# pcb_knx-valve-control_v1_2.net
KiCad netlist of a schematic drawn in EasyEDA
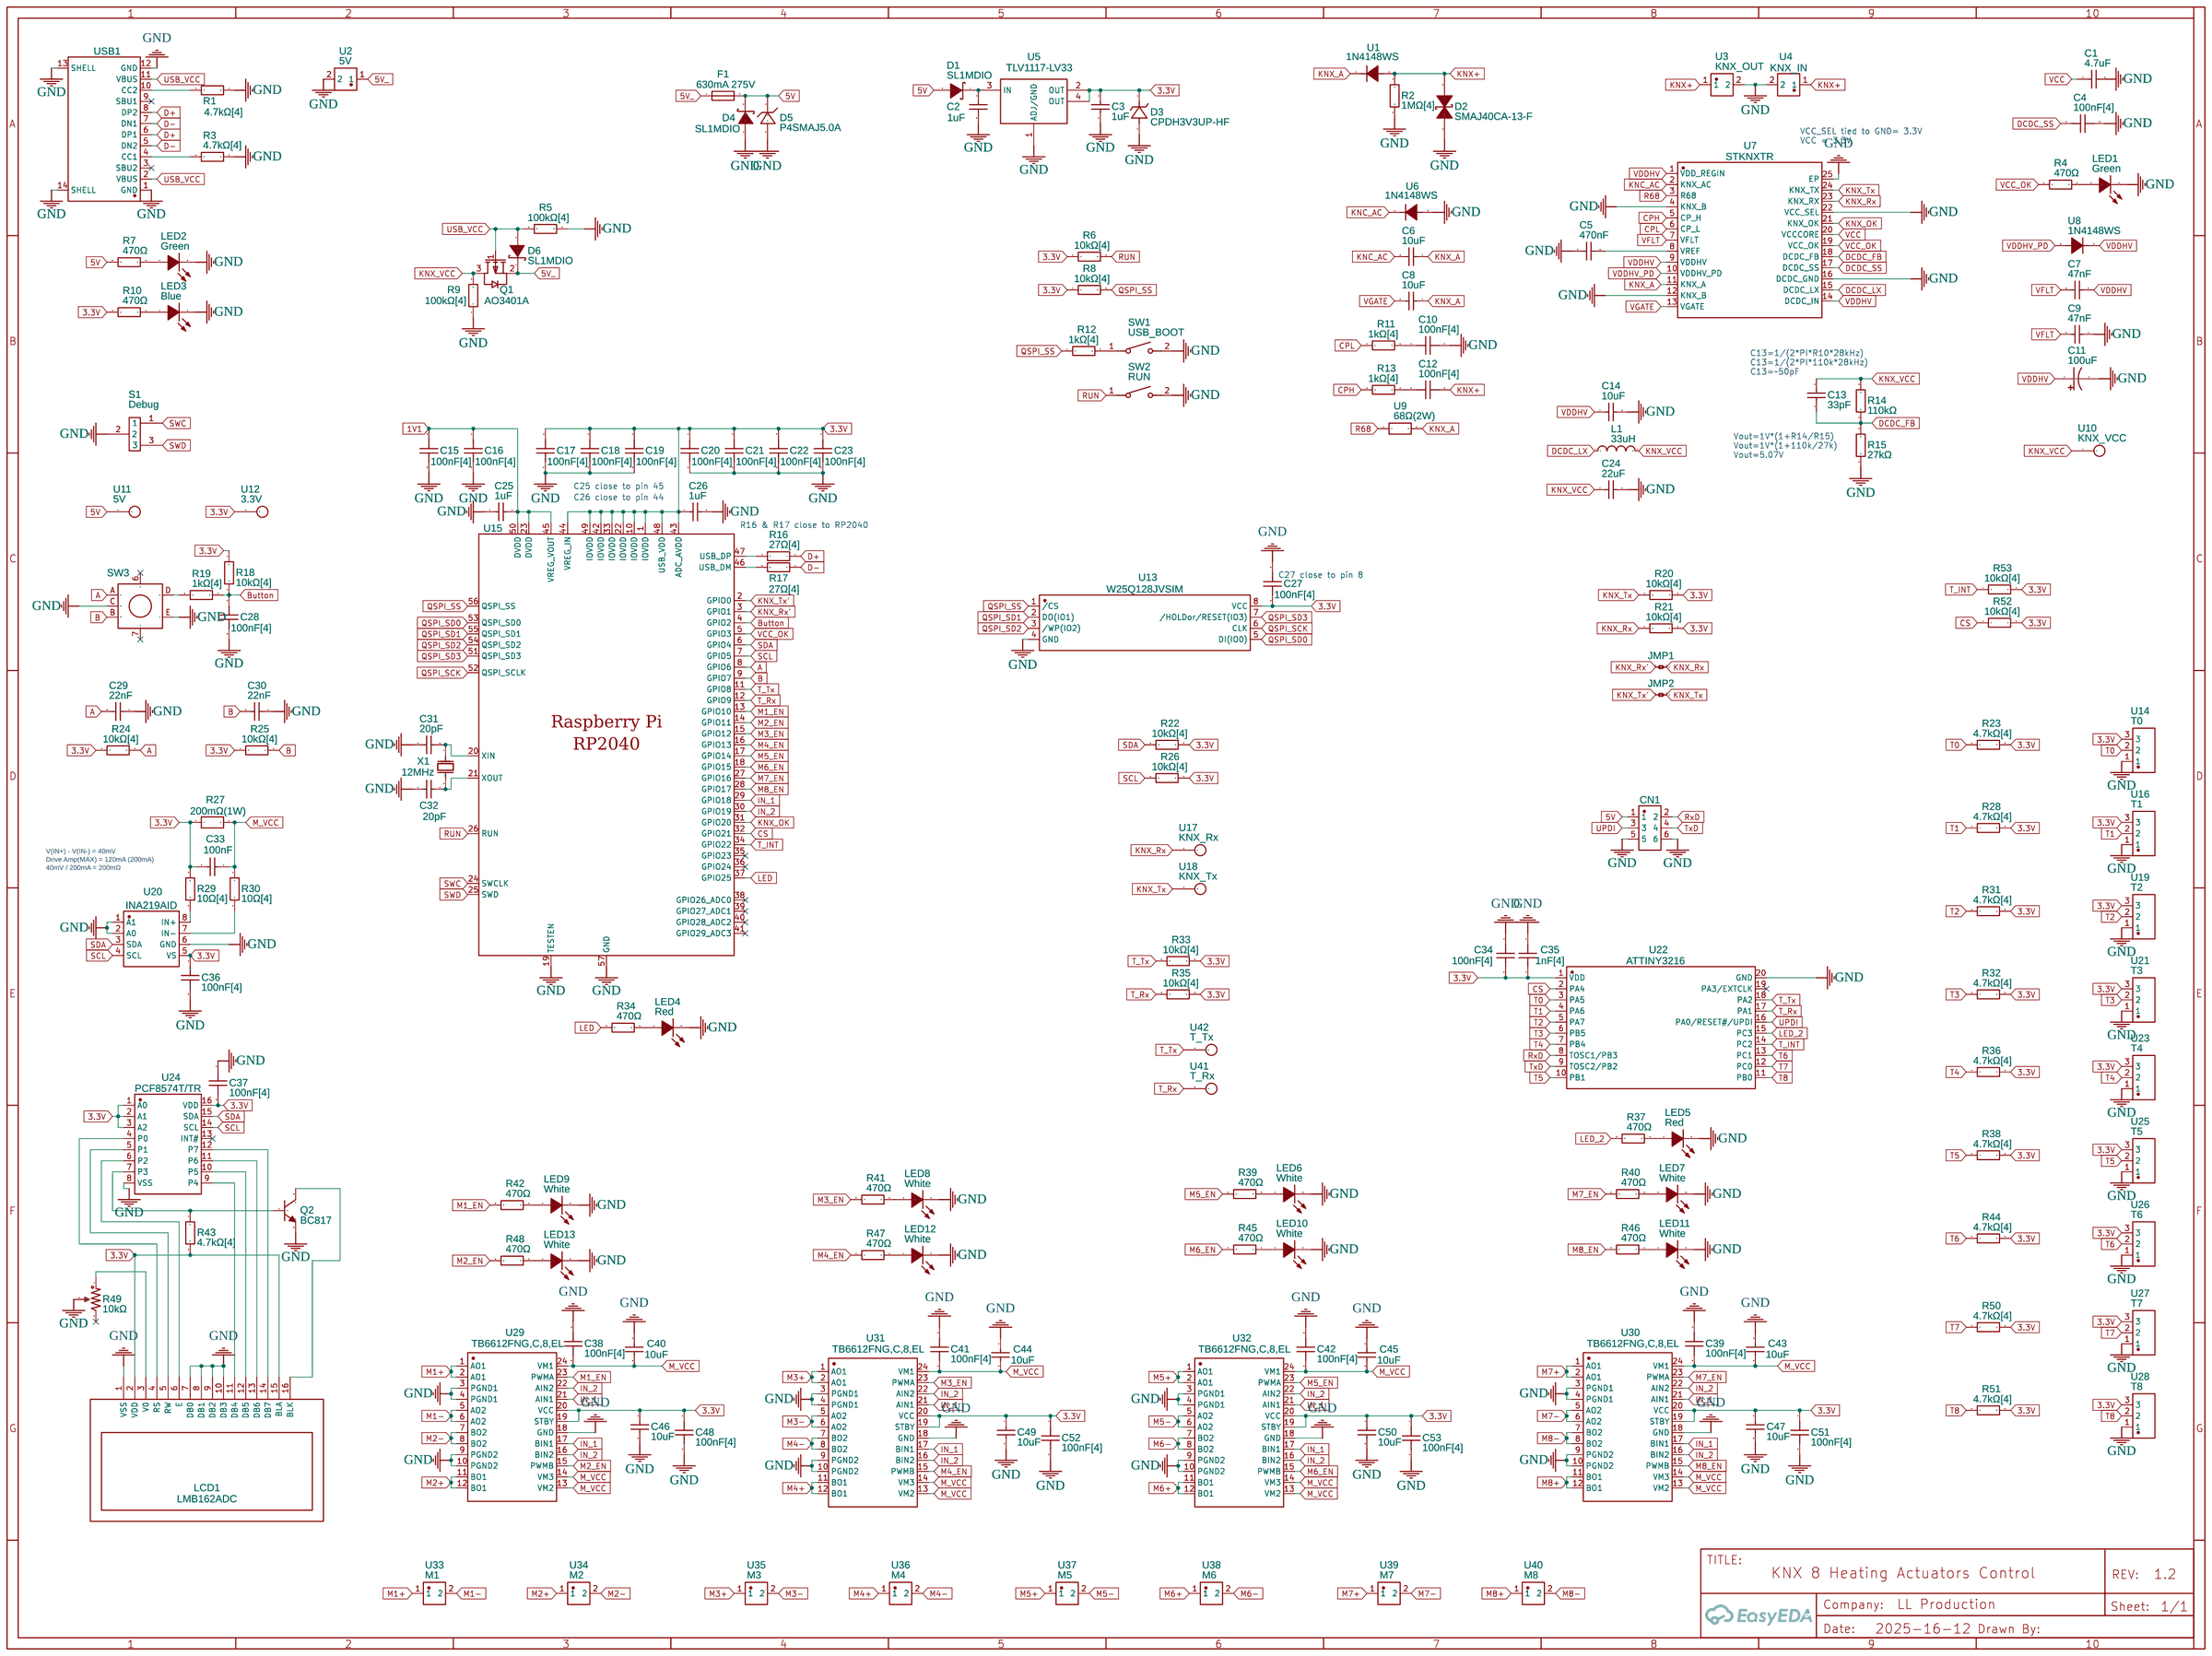
[diagram p0: schematic sheet]

(export (version "E")
  (design (tool "Eeschema 10.0.6"))
  (components
    (comp (ref "C1")
      (value "4.7uF")
      (fields (field (name "Manufacturer Part") "CC0603KRX7R9BB103") (field (name "Manufacturer") "YAGEO"))
      (libsource (lib "") (part "CC0603KRX7R9BB103_2"))
    )
    (comp (ref "C2")
      (value "1uF")
      (fields (field (name "Manufacturer Part") "CC0603KRX7R9BB103") (field (name "Manufacturer") "YAGEO"))
      (libsource (lib "") (part "CC0603KRX7R9BB103_3"))
    )
    (comp (ref "C3")
      (value "1uF")
      (fields (field (name "Manufacturer Part") "CC0603KRX7R9BB103") (field (name "Manufacturer") "YAGEO"))
      (libsource (lib "") (part "CC0603KRX7R9BB103_3"))
    )
    (comp (ref "C4")
      (value "100nF[4]")
      (fields
        (field (name "Manufacturer Part") "GRM155R71H104KE14D")
        (field (name "Manufacturer") "muRata(村田)")
      )
      (libsource (lib "") (part "GRM155R71H104KE14D_1"))
    )
    (comp (ref "C5")
      (value "470nF")
      (fields (field (name "Manufacturer Part") "CC0603KRX7R9BB103") (field (name "Manufacturer") "YAGEO"))
      (libsource (lib "") (part "CC0603KRX7R9BB103_1"))
    )
    (comp (ref "C6")
      (value "10uF")
      (fields (field (name "Manufacturer Part") "CC0603KRX7R9BB103") (field (name "Manufacturer") "YAGEO"))
      (libsource (lib "") (part "CC0603KRX7R9BB103_2"))
    )
    (comp (ref "C7")
      (value "47nF")
      (fields (field (name "Manufacturer Part") "CC0603KRX7R9BB103") (field (name "Manufacturer") "YAGEO"))
      (libsource (lib "") (part "CC0603KRX7R9BB103_2"))
    )
    (comp (ref "C8")
      (value "10uF")
      (fields (field (name "Manufacturer Part") "CC0603KRX7R9BB103") (field (name "Manufacturer") "YAGEO"))
      (libsource (lib "") (part "CC0603KRX7R9BB103_2"))
    )
    (comp (ref "C9")
      (value "47nF")
      (fields (field (name "Manufacturer Part") "CC0603KRX7R9BB103") (field (name "Manufacturer") "YAGEO"))
      (libsource (lib "") (part "CC0603KRX7R9BB103_2"))
    )
    (comp (ref "C10")
      (value "100nF[4]")
      (fields
        (field (name "Manufacturer Part") "GRM155R71H104KE14D")
        (field (name "Manufacturer") "muRata(村田)")
      )
      (libsource (lib "") (part "GRM155R71H104KE14D_1"))
    )
    (comp (ref "C11")
      (value "100uF")
      (fields (field (name "Manufacturer Part") "VEJ101M1HTR-0810") (field (name "Manufacturer") "Lelon(立隆)"))
      (libsource (lib "") (part "VEJ101M1HTR-0810"))
    )
    (comp (ref "C12")
      (value "100nF[4]")
      (fields
        (field (name "Manufacturer Part") "GRM155R71H104KE14D")
        (field (name "Manufacturer") "muRata(村田)")
      )
      (libsource (lib "") (part "GRM155R71H104KE14D_1"))
    )
    (comp (ref "C13")
      (value "33pF")
      (fields (field (name "Manufacturer Part") "CC0603KRX7R9BB103") (field (name "Manufacturer") "YAGEO"))
      (libsource (lib "") (part "CC0603KRX7R9BB103"))
    )
    (comp (ref "C14")
      (value "10uF")
      (fields (field (name "Manufacturer Part") "CC0603KRX7R9BB103") (field (name "Manufacturer") "YAGEO"))
      (libsource (lib "") (part "CC0603KRX7R9BB103_1"))
    )
    (comp (ref "C15")
      (value "100nF[4]")
      (fields
        (field (name "Manufacturer Part") "GRM155R71H104KE14D")
        (field (name "Manufacturer") "muRata(村田)")
      )
      (libsource (lib "") (part "GRM155R71H104KE14D"))
    )
    (comp (ref "C16")
      (value "100nF[4]")
      (fields
        (field (name "Manufacturer Part") "GRM155R71H104KE14D")
        (field (name "Manufacturer") "muRata(村田)")
      )
      (libsource (lib "") (part "GRM155R71H104KE14D"))
    )
    (comp (ref "C17")
      (value "100nF[4]")
      (fields
        (field (name "Manufacturer Part") "GRM155R71H104KE14D")
        (field (name "Manufacturer") "muRata(村田)")
      )
      (libsource (lib "") (part "GRM155R71H104KE14D"))
    )
    (comp (ref "C18")
      (value "100nF[4]")
      (fields
        (field (name "Manufacturer Part") "GRM155R71H104KE14D")
        (field (name "Manufacturer") "muRata(村田)")
      )
      (libsource (lib "") (part "GRM155R71H104KE14D"))
    )
    (comp (ref "C19")
      (value "100nF[4]")
      (fields
        (field (name "Manufacturer Part") "GRM155R71H104KE14D")
        (field (name "Manufacturer") "muRata(村田)")
      )
      (libsource (lib "") (part "GRM155R71H104KE14D"))
    )
    (comp (ref "C20")
      (value "100nF[4]")
      (fields
        (field (name "Manufacturer Part") "GRM155R71H104KE14D")
        (field (name "Manufacturer") "muRata(村田)")
      )
      (libsource (lib "") (part "GRM155R71H104KE14D"))
    )
    (comp (ref "C21")
      (value "100nF[4]")
      (fields
        (field (name "Manufacturer Part") "GRM155R71H104KE14D")
        (field (name "Manufacturer") "muRata(村田)")
      )
      (libsource (lib "") (part "GRM155R71H104KE14D"))
    )
    (comp (ref "C22")
      (value "100nF[4]")
      (fields
        (field (name "Manufacturer Part") "GRM155R71H104KE14D")
        (field (name "Manufacturer") "muRata(村田)")
      )
      (libsource (lib "") (part "GRM155R71H104KE14D"))
    )
    (comp (ref "C23")
      (value "100nF[4]")
      (fields
        (field (name "Manufacturer Part") "GRM155R71H104KE14D")
        (field (name "Manufacturer") "muRata(村田)")
      )
      (libsource (lib "") (part "GRM155R71H104KE14D"))
    )
    (comp (ref "C24")
      (value "22uF")
      (fields (field (name "Manufacturer Part") "CC0603KRX7R9BB103") (field (name "Manufacturer") "YAGEO"))
      (libsource (lib "") (part "CC0603KRX7R9BB103_1"))
    )
    (comp (ref "C25")
      (value "1uF")
      (fields (field (name "Manufacturer Part") "CC0603KRX7R9BB103") (field (name "Manufacturer") "YAGEO"))
      (libsource (lib "") (part "CC0603KRX7R9BB103_1"))
    )
    (comp (ref "C26")
      (value "1uF")
      (fields (field (name "Manufacturer Part") "CC0603KRX7R9BB103") (field (name "Manufacturer") "YAGEO"))
      (libsource (lib "") (part "CC0603KRX7R9BB103_1"))
    )
    (comp (ref "C27")
      (value "100nF[4]")
      (fields
        (field (name "Manufacturer Part") "GRM155R71H104KE14D")
        (field (name "Manufacturer") "muRata(村田)")
      )
      (libsource (lib "") (part "GRM155R71H104KE14D"))
    )
    (comp (ref "C28")
      (value "100nF[4]")
      (fields
        (field (name "Manufacturer Part") "GRM155R71H104KE14D")
        (field (name "Manufacturer") "muRata(村田)")
      )
      (libsource (lib "") (part "GRM155R71H104KE14D"))
    )
    (comp (ref "C29")
      (value "22nF")
      (fields (field (name "Manufacturer Part") "CC0603KRX7R9BB103") (field (name "Manufacturer") "YAGEO"))
      (libsource (lib "") (part "CC0603KRX7R9BB103_2"))
    )
    (comp (ref "C30")
      (value "22nF")
      (fields (field (name "Manufacturer Part") "CC0603KRX7R9BB103") (field (name "Manufacturer") "YAGEO"))
      (libsource (lib "") (part "CC0603KRX7R9BB103_2"))
    )
    (comp (ref "C31")
      (value "20pF")
      (fields (field (name "Manufacturer Part") "CC0603KRX7R9BB103") (field (name "Manufacturer") "YAGEO"))
      (libsource (lib "") (part "CC0603KRX7R9BB103_1"))
    )
    (comp (ref "C32")
      (value "20pF")
      (fields (field (name "Manufacturer Part") "CC0603KRX7R9BB103") (field (name "Manufacturer") "YAGEO"))
      (libsource (lib "") (part "CC0603KRX7R9BB103_1"))
    )
    (comp (ref "C33")
      (value "100nF")
      (fields (field (name "Manufacturer Part") "CC0603KRX7R9BB103") (field (name "Manufacturer") "YAGEO"))
      (libsource (lib "") (part "CC0603KRX7R9BB103_2"))
    )
    (comp (ref "C34")
      (value "100nF[4]")
      (fields
        (field (name "Manufacturer Part") "GRM155R71H104KE14D")
        (field (name "Manufacturer") "muRata(村田)")
      )
      (libsource (lib "") (part "GRM155R71H104KE14D"))
    )
    (comp (ref "C35")
      (value "1nF[4]")
      (fields
        (field (name "Manufacturer Part") "GRM155R71H104KE14D")
        (field (name "Manufacturer") "muRata(村田)")
      )
      (libsource (lib "") (part "GRM155R71H104KE14D"))
    )
    (comp (ref "C36")
      (value "100nF[4]")
      (fields
        (field (name "Manufacturer Part") "GRM155R71H104KE14D")
        (field (name "Manufacturer") "muRata(村田)")
      )
      (libsource (lib "") (part "GRM155R71H104KE14D"))
    )
    (comp (ref "C37")
      (value "100nF[4]")
      (fields
        (field (name "Manufacturer Part") "GRM155R71H104KE14D")
        (field (name "Manufacturer") "muRata(村田)")
      )
      (libsource (lib "") (part "GRM155R71H104KE14D"))
    )
    (comp (ref "C38")
      (value "100nF[4]")
      (fields
        (field (name "Manufacturer Part") "GRM155R71H104KE14D")
        (field (name "Manufacturer") "muRata(村田)")
      )
      (libsource (lib "") (part "GRM155R71H104KE14D"))
    )
    (comp (ref "C39")
      (value "100nF[4]")
      (fields
        (field (name "Manufacturer Part") "GRM155R71H104KE14D")
        (field (name "Manufacturer") "muRata(村田)")
      )
      (libsource (lib "") (part "GRM155R71H104KE14D"))
    )
    (comp (ref "C40")
      (value "10uF")
      (fields (field (name "Manufacturer Part") "CC0603KRX7R9BB103") (field (name "Manufacturer") "YAGEO"))
      (libsource (lib "") (part "CC0603KRX7R9BB103"))
    )
    (comp (ref "C41")
      (value "100nF[4]")
      (fields
        (field (name "Manufacturer Part") "GRM155R71H104KE14D")
        (field (name "Manufacturer") "muRata(村田)")
      )
      (libsource (lib "") (part "GRM155R71H104KE14D"))
    )
    (comp (ref "C42")
      (value "100nF[4]")
      (fields
        (field (name "Manufacturer Part") "GRM155R71H104KE14D")
        (field (name "Manufacturer") "muRata(村田)")
      )
      (libsource (lib "") (part "GRM155R71H104KE14D"))
    )
    (comp (ref "C43")
      (value "10uF")
      (fields (field (name "Manufacturer Part") "CC0603KRX7R9BB103") (field (name "Manufacturer") "YAGEO"))
      (libsource (lib "") (part "CC0603KRX7R9BB103"))
    )
    (comp (ref "C44")
      (value "10uF")
      (fields (field (name "Manufacturer Part") "CC0603KRX7R9BB103") (field (name "Manufacturer") "YAGEO"))
      (libsource (lib "") (part "CC0603KRX7R9BB103"))
    )
    (comp (ref "C45")
      (value "10uF")
      (fields (field (name "Manufacturer Part") "CC0603KRX7R9BB103") (field (name "Manufacturer") "YAGEO"))
      (libsource (lib "") (part "CC0603KRX7R9BB103"))
    )
    (comp (ref "C46")
      (value "10uF")
      (fields (field (name "Manufacturer Part") "CC0603KRX7R9BB103") (field (name "Manufacturer") "YAGEO"))
      (libsource (lib "") (part "CC0603KRX7R9BB103"))
    )
    (comp (ref "C47")
      (value "10uF")
      (fields (field (name "Manufacturer Part") "CC0603KRX7R9BB103") (field (name "Manufacturer") "YAGEO"))
      (libsource (lib "") (part "CC0603KRX7R9BB103"))
    )
    (comp (ref "C48")
      (value "100nF[4]")
      (fields
        (field (name "Manufacturer Part") "GRM155R71H104KE14D")
        (field (name "Manufacturer") "muRata(村田)")
      )
      (libsource (lib "") (part "GRM155R71H104KE14D"))
    )
    (comp (ref "C49")
      (value "10uF")
      (fields (field (name "Manufacturer Part") "CC0603KRX7R9BB103") (field (name "Manufacturer") "YAGEO"))
      (libsource (lib "") (part "CC0603KRX7R9BB103"))
    )
    (comp (ref "C50")
      (value "10uF")
      (fields (field (name "Manufacturer Part") "CC0603KRX7R9BB103") (field (name "Manufacturer") "YAGEO"))
      (libsource (lib "") (part "CC0603KRX7R9BB103"))
    )
    (comp (ref "C51")
      (value "100nF[4]")
      (fields
        (field (name "Manufacturer Part") "GRM155R71H104KE14D")
        (field (name "Manufacturer") "muRata(村田)")
      )
      (libsource (lib "") (part "GRM155R71H104KE14D"))
    )
    (comp (ref "C52")
      (value "100nF[4]")
      (fields
        (field (name "Manufacturer Part") "GRM155R71H104KE14D")
        (field (name "Manufacturer") "muRata(村田)")
      )
      (libsource (lib "") (part "GRM155R71H104KE14D"))
    )
    (comp (ref "C53")
      (value "100nF[4]")
      (fields
        (field (name "Manufacturer Part") "GRM155R71H104KE14D")
        (field (name "Manufacturer") "muRata(村田)")
      )
      (libsource (lib "") (part "GRM155R71H104KE14D"))
    )
    (comp (ref "CN1")
      (value "321006SG0ABK00A01")
      (fields (field (name "Manufacturer") "JILN(锦凌)"))
      (libsource (lib "") (part "321006SG0ABK00A01"))
    )
    (comp (ref "D1")
      (value "SL1MDIO")
      (fields (field (name "Manufacturer Part") "1N5819HW-7-F") (field (name "Manufacturer") "DIODES(美台)"))
      (libsource (lib "") (part "1N5819HW-7-F"))
    )
    (comp (ref "D2")
      (value "SMAJ40CA-13-F")
      (fields (field (name "Manufacturer") "DIODES(美台)"))
      (libsource (lib "") (part "SMAJ40CA-13-F"))
    )
    (comp (ref "D3")
      (value "CPDH3V3UP-HF")
      (fields (field (name "Manufacturer Part") "SOD-523"))
      (libsource (lib "") (part "SOD-523"))
    )
    (comp (ref "D4")
      (value "SL1MDIO")
      (fields (field (name "Manufacturer Part") "1N5819HW-7-F") (field (name "Manufacturer") "DIODES(美台)"))
      (libsource (lib "") (part "1N5819HW-7-F_1"))
    )
    (comp (ref "D5")
      (value "P4SMAJ5.0A")
      (fields
        (field (name "Manufacturer Part") "P4SMAJ12A_R1_00001")
        (field (name "Manufacturer") "PANJIT(强茂)")
      )
      (libsource (lib "") (part "P4SMAJ12A-PEC"))
    )
    (comp (ref "D6")
      (value "SL1MDIO")
      (fields (field (name "Manufacturer Part") "1N5819HW-7-F") (field (name "Manufacturer") "DIODES(美台)"))
      (libsource (lib "") (part "1N5819HW-7-F_2"))
    )
    (comp (ref "F1")
      (value "630mA 275V")
      (fields (field (name "Manufacturer Part") "S1032-F-60.0A") (field (name "Manufacturer") "SART(萨特)"))
      (libsource (lib "") (part "S1032-F-60.0A"))
    )
    (comp (ref "JMP1") (value "Rx") (libsource (lib "") (part "JMP-2-NO-0603")))
    (comp (ref "JMP2") (value "Rx") (libsource (lib "") (part "JMP-2-NO-0603")))
    (comp (ref "L1")
      (value "33uH")
      (fields
        (field (name "Manufacturer Part") "NR5040T330M")
        (field (name "Manufacturer") "TAIYO YUDEN(太诱)")
      )
      (libsource (lib "") (part "NR5040T330M"))
    )
    (comp (ref "LCD1")
      (value "LMB162ADC")
      (fields (field (name "Manufacturer") "TOPWAY"))
      (libsource (lib "") (part "LMB162ADC"))
    )
    (comp (ref "LED1")
      (value "Green")
      (fields (field (name "Manufacturer Part") "SZYY0603R") (field (name "Manufacturer") "yongyu(永裕光电)"))
      (libsource (lib "") (part "SZYY0603R"))
    )
    (comp (ref "LED2")
      (value "Green")
      (fields (field (name "Manufacturer Part") "SZYY0603R") (field (name "Manufacturer") "yongyu(永裕光电)"))
      (libsource (lib "") (part "SZYY0603R"))
    )
    (comp (ref "LED3")
      (value "Blue")
      (fields (field (name "Manufacturer Part") "SZYY0603R") (field (name "Manufacturer") "yongyu(永裕光电)"))
      (libsource (lib "") (part "SZYY0603R"))
    )
    (comp (ref "LED4")
      (value "Red")
      (fields (field (name "Manufacturer Part") "SZYY0603R") (field (name "Manufacturer") "yongyu(永裕光电)"))
      (libsource (lib "") (part "SZYY0603R"))
    )
    (comp (ref "LED5")
      (value "Red")
      (fields (field (name "Manufacturer Part") "SZYY0603R") (field (name "Manufacturer") "yongyu(永裕光电)"))
      (libsource (lib "") (part "SZYY0603R"))
    )
    (comp (ref "LED6")
      (value "White")
      (fields (field (name "Manufacturer Part") "SZYY0603R") (field (name "Manufacturer") "yongyu(永裕光电)"))
      (libsource (lib "") (part "SZYY0603R"))
    )
    (comp (ref "LED7")
      (value "White")
      (fields (field (name "Manufacturer Part") "SZYY0603R") (field (name "Manufacturer") "yongyu(永裕光电)"))
      (libsource (lib "") (part "SZYY0603R"))
    )
    (comp (ref "LED8")
      (value "White")
      (fields (field (name "Manufacturer Part") "SZYY0603R") (field (name "Manufacturer") "yongyu(永裕光电)"))
      (libsource (lib "") (part "SZYY0603R"))
    )
    (comp (ref "LED9")
      (value "White")
      (fields (field (name "Manufacturer Part") "SZYY0603R") (field (name "Manufacturer") "yongyu(永裕光电)"))
      (libsource (lib "") (part "SZYY0603R"))
    )
    (comp (ref "LED10")
      (value "White")
      (fields (field (name "Manufacturer Part") "SZYY0603R") (field (name "Manufacturer") "yongyu(永裕光电)"))
      (libsource (lib "") (part "SZYY0603R"))
    )
    (comp (ref "LED11")
      (value "White")
      (fields (field (name "Manufacturer Part") "SZYY0603R") (field (name "Manufacturer") "yongyu(永裕光电)"))
      (libsource (lib "") (part "SZYY0603R"))
    )
    (comp (ref "LED12")
      (value "White")
      (fields (field (name "Manufacturer Part") "SZYY0603R") (field (name "Manufacturer") "yongyu(永裕光电)"))
      (libsource (lib "") (part "SZYY0603R"))
    )
    (comp (ref "LED13")
      (value "White")
      (fields (field (name "Manufacturer Part") "SZYY0603R") (field (name "Manufacturer") "yongyu(永裕光电)"))
      (libsource (lib "") (part "SZYY0603R"))
    )
    (comp (ref "Q1")
      (value "AO3401A")
      (fields (field (name "Manufacturer") "HUASHUO(华朔)"))
      (libsource (lib "") (part "AO3401A_C700954"))
    )
    (comp (ref "Q2")
      (value "BC817")
      (fields (field (name "Manufacturer Part") "BC817-40,215") (field (name "Manufacturer") "Nexperia(安世)"))
      (libsource (lib "") (part "BC817-40,215"))
    )
    (comp (ref "R1")
      (value "4.7kΩ[4]")
      (fields
        (field (name "Manufacturer Part") "0402WGF1002TCE")
        (field (name "Manufacturer") "UNI-ROYAL(厚声)")
      )
      (libsource (lib "") (part "0402WGF1002TCE_2"))
    )
    (comp (ref "R2")
      (value "1MΩ[4]")
      (fields
        (field (name "Manufacturer Part") "0402WGF1002TCE")
        (field (name "Manufacturer") "UNI-ROYAL(厚声)")
      )
      (libsource (lib "") (part "0402WGF1002TCE_3"))
    )
    (comp (ref "R3")
      (value "4.7kΩ[4]")
      (fields
        (field (name "Manufacturer Part") "0402WGF1002TCE")
        (field (name "Manufacturer") "UNI-ROYAL(厚声)")
      )
      (libsource (lib "") (part "0402WGF1002TCE_2"))
    )
    (comp (ref "R4")
      (value "470Ω")
      (fields (field (name "Manufacturer Part") "CR0603FA1001G") (field (name "Manufacturer") "LIZ(丽智电子)"))
      (libsource (lib "") (part "CR0603FA1001G_C126900"))
    )
    (comp (ref "R5")
      (value "100kΩ[4]")
      (fields
        (field (name "Manufacturer Part") "0402WGF1002TCE")
        (field (name "Manufacturer") "UNI-ROYAL(厚声)")
      )
      (libsource (lib "") (part "0402WGF1002TCE"))
    )
    (comp (ref "R6")
      (value "10kΩ[4]")
      (fields
        (field (name "Manufacturer Part") "0402WGF1002TCE")
        (field (name "Manufacturer") "UNI-ROYAL(厚声)")
      )
      (libsource (lib "") (part "0402WGF1002TCE"))
    )
    (comp (ref "R7")
      (value "470Ω")
      (fields (field (name "Manufacturer Part") "CR0603FA1001G") (field (name "Manufacturer") "LIZ(丽智电子)"))
      (libsource (lib "") (part "CR0603FA1001G_C126900"))
    )
    (comp (ref "R8")
      (value "10kΩ[4]")
      (fields
        (field (name "Manufacturer Part") "0402WGF1002TCE")
        (field (name "Manufacturer") "UNI-ROYAL(厚声)")
      )
      (libsource (lib "") (part "0402WGF1002TCE"))
    )
    (comp (ref "R9")
      (value "100kΩ[4]")
      (fields
        (field (name "Manufacturer Part") "0402WGF1002TCE")
        (field (name "Manufacturer") "UNI-ROYAL(厚声)")
      )
      (libsource (lib "") (part "0402WGF1002TCE_1"))
    )
    (comp (ref "R10")
      (value "470Ω")
      (fields (field (name "Manufacturer Part") "CR0603FA1001G") (field (name "Manufacturer") "LIZ(丽智电子)"))
      (libsource (lib "") (part "CR0603FA1001G_C126900"))
    )
    (comp (ref "R11")
      (value "1kΩ[4]")
      (fields
        (field (name "Manufacturer Part") "0402WGF1002TCE")
        (field (name "Manufacturer") "UNI-ROYAL(厚声)")
      )
      (libsource (lib "") (part "0402WGF1002TCE"))
    )
    (comp (ref "R12")
      (value "1kΩ[4]")
      (fields
        (field (name "Manufacturer Part") "0402WGF1002TCE")
        (field (name "Manufacturer") "UNI-ROYAL(厚声)")
      )
      (libsource (lib "") (part "0402WGF1002TCE"))
    )
    (comp (ref "R13")
      (value "1kΩ[4]")
      (fields
        (field (name "Manufacturer Part") "0402WGF1002TCE")
        (field (name "Manufacturer") "UNI-ROYAL(厚声)")
      )
      (libsource (lib "") (part "0402WGF1002TCE"))
    )
    (comp (ref "R14")
      (value "110kΩ")
      (fields (field (name "Manufacturer Part") "CR0603FA1001G") (field (name "Manufacturer") "LIZ(丽智电子)"))
      (libsource (lib "") (part "CR0603FA1001G_C126900_1"))
    )
    (comp (ref "R15")
      (value "27kΩ")
      (fields (field (name "Manufacturer Part") "CR0603FA1001G") (field (name "Manufacturer") "LIZ(丽智电子)"))
      (libsource (lib "") (part "CR0603FA1001G_C126900_1"))
    )
    (comp (ref "R16")
      (value "27Ω[4]")
      (fields
        (field (name "Manufacturer Part") "0402WGF1002TCE")
        (field (name "Manufacturer") "UNI-ROYAL(厚声)")
      )
      (libsource (lib "") (part "0402WGF1002TCE_2"))
    )
    (comp (ref "R17")
      (value "27Ω[4]")
      (fields
        (field (name "Manufacturer Part") "0402WGF1002TCE")
        (field (name "Manufacturer") "UNI-ROYAL(厚声)")
      )
      (libsource (lib "") (part "0402WGF1002TCE_2"))
    )
    (comp (ref "R18")
      (value "10kΩ[4]")
      (fields
        (field (name "Manufacturer Part") "0402WGF1002TCE")
        (field (name "Manufacturer") "UNI-ROYAL(厚声)")
      )
      (libsource (lib "") (part "0402WGF1002TCE_3"))
    )
    (comp (ref "R19")
      (value "1kΩ[4]")
      (fields
        (field (name "Manufacturer Part") "0402WGF1002TCE")
        (field (name "Manufacturer") "UNI-ROYAL(厚声)")
      )
      (libsource (lib "") (part "0402WGF1002TCE_2"))
    )
    (comp (ref "R20")
      (value "10kΩ[4]")
      (fields
        (field (name "Manufacturer Part") "0402WGF1002TCE")
        (field (name "Manufacturer") "UNI-ROYAL(厚声)")
      )
      (libsource (lib "") (part "0402WGF1002TCE"))
    )
    (comp (ref "R21")
      (value "10kΩ[4]")
      (fields
        (field (name "Manufacturer Part") "0402WGF1002TCE")
        (field (name "Manufacturer") "UNI-ROYAL(厚声)")
      )
      (libsource (lib "") (part "0402WGF1002TCE"))
    )
    (comp (ref "R22")
      (value "10kΩ[4]")
      (fields
        (field (name "Manufacturer Part") "0402WGF1002TCE")
        (field (name "Manufacturer") "UNI-ROYAL(厚声)")
      )
      (libsource (lib "") (part "0402WGF1002TCE"))
    )
    (comp (ref "R23")
      (value "4.7kΩ[4]")
      (fields
        (field (name "Manufacturer Part") "0402WGF1002TCE")
        (field (name "Manufacturer") "UNI-ROYAL(厚声)")
      )
      (libsource (lib "") (part "0402WGF1002TCE"))
    )
    (comp (ref "R24")
      (value "10kΩ[4]")
      (fields
        (field (name "Manufacturer Part") "0402WGF1002TCE")
        (field (name "Manufacturer") "UNI-ROYAL(厚声)")
      )
      (libsource (lib "") (part "0402WGF1002TCE"))
    )
    (comp (ref "R25")
      (value "10kΩ[4]")
      (fields
        (field (name "Manufacturer Part") "0402WGF1002TCE")
        (field (name "Manufacturer") "UNI-ROYAL(厚声)")
      )
      (libsource (lib "") (part "0402WGF1002TCE"))
    )
    (comp (ref "R26")
      (value "10kΩ[4]")
      (fields
        (field (name "Manufacturer Part") "0402WGF1002TCE")
        (field (name "Manufacturer") "UNI-ROYAL(厚声)")
      )
      (libsource (lib "") (part "0402WGF1002TCE"))
    )
    (comp (ref "R27")
      (value "200mΩ(1W)")
      (fields (field (name "Manufacturer Part") "SCR1206F1M1") (field (name "Manufacturer") "VO(翔胜)"))
      (libsource (lib "") (part "SCR1206F1M1"))
    )
    (comp (ref "R28")
      (value "4.7kΩ[4]")
      (fields
        (field (name "Manufacturer Part") "0402WGF1002TCE")
        (field (name "Manufacturer") "UNI-ROYAL(厚声)")
      )
      (libsource (lib "") (part "0402WGF1002TCE"))
    )
    (comp (ref "R29")
      (value "10Ω[4]")
      (fields
        (field (name "Manufacturer Part") "0402WGF1002TCE")
        (field (name "Manufacturer") "UNI-ROYAL(厚声)")
      )
      (libsource (lib "") (part "0402WGF1002TCE_3"))
    )
    (comp (ref "R30")
      (value "10Ω[4]")
      (fields
        (field (name "Manufacturer Part") "0402WGF1002TCE")
        (field (name "Manufacturer") "UNI-ROYAL(厚声)")
      )
      (libsource (lib "") (part "0402WGF1002TCE_3"))
    )
    (comp (ref "R31")
      (value "4.7kΩ[4]")
      (fields
        (field (name "Manufacturer Part") "0402WGF1002TCE")
        (field (name "Manufacturer") "UNI-ROYAL(厚声)")
      )
      (libsource (lib "") (part "0402WGF1002TCE"))
    )
    (comp (ref "R32")
      (value "4.7kΩ[4]")
      (fields
        (field (name "Manufacturer Part") "0402WGF1002TCE")
        (field (name "Manufacturer") "UNI-ROYAL(厚声)")
      )
      (libsource (lib "") (part "0402WGF1002TCE"))
    )
    (comp (ref "R33")
      (value "10kΩ[4]")
      (fields
        (field (name "Manufacturer Part") "0402WGF1002TCE")
        (field (name "Manufacturer") "UNI-ROYAL(厚声)")
      )
      (libsource (lib "") (part "0402WGF1002TCE"))
    )
    (comp (ref "R34")
      (value "470Ω")
      (fields (field (name "Manufacturer Part") "CR0603FA1001G") (field (name "Manufacturer") "LIZ(丽智电子)"))
      (libsource (lib "") (part "CR0603FA1001G_C126900"))
    )
    (comp (ref "R35")
      (value "10kΩ[4]")
      (fields
        (field (name "Manufacturer Part") "0402WGF1002TCE")
        (field (name "Manufacturer") "UNI-ROYAL(厚声)")
      )
      (libsource (lib "") (part "0402WGF1002TCE"))
    )
    (comp (ref "R36")
      (value "4.7kΩ[4]")
      (fields
        (field (name "Manufacturer Part") "0402WGF1002TCE")
        (field (name "Manufacturer") "UNI-ROYAL(厚声)")
      )
      (libsource (lib "") (part "0402WGF1002TCE"))
    )
    (comp (ref "R37")
      (value "470Ω")
      (fields (field (name "Manufacturer Part") "CR0603FA1001G") (field (name "Manufacturer") "LIZ(丽智电子)"))
      (libsource (lib "") (part "CR0603FA1001G_C126900"))
    )
    (comp (ref "R38")
      (value "4.7kΩ[4]")
      (fields
        (field (name "Manufacturer Part") "0402WGF1002TCE")
        (field (name "Manufacturer") "UNI-ROYAL(厚声)")
      )
      (libsource (lib "") (part "0402WGF1002TCE"))
    )
    (comp (ref "R39")
      (value "470Ω")
      (fields (field (name "Manufacturer Part") "CR0603FA1001G") (field (name "Manufacturer") "LIZ(丽智电子)"))
      (libsource (lib "") (part "CR0603FA1001G_C126900"))
    )
    (comp (ref "R40")
      (value "470Ω")
      (fields (field (name "Manufacturer Part") "CR0603FA1001G") (field (name "Manufacturer") "LIZ(丽智电子)"))
      (libsource (lib "") (part "CR0603FA1001G_C126900"))
    )
    (comp (ref "R41")
      (value "470Ω")
      (fields (field (name "Manufacturer Part") "CR0603FA1001G") (field (name "Manufacturer") "LIZ(丽智电子)"))
      (libsource (lib "") (part "CR0603FA1001G_C126900"))
    )
    (comp (ref "R42")
      (value "470Ω")
      (fields (field (name "Manufacturer Part") "CR0603FA1001G") (field (name "Manufacturer") "LIZ(丽智电子)"))
      (libsource (lib "") (part "CR0603FA1001G_C126900"))
    )
    (comp (ref "R43")
      (value "4.7kΩ[4]")
      (fields
        (field (name "Manufacturer Part") "0402WGF1002TCE")
        (field (name "Manufacturer") "UNI-ROYAL(厚声)")
      )
      (libsource (lib "") (part "0402WGF1002TCE_3"))
    )
    (comp (ref "R44")
      (value "4.7kΩ[4]")
      (fields
        (field (name "Manufacturer Part") "0402WGF1002TCE")
        (field (name "Manufacturer") "UNI-ROYAL(厚声)")
      )
      (libsource (lib "") (part "0402WGF1002TCE"))
    )
    (comp (ref "R45")
      (value "470Ω")
      (fields (field (name "Manufacturer Part") "CR0603FA1001G") (field (name "Manufacturer") "LIZ(丽智电子)"))
      (libsource (lib "") (part "CR0603FA1001G_C126900"))
    )
    (comp (ref "R46")
      (value "470Ω")
      (fields (field (name "Manufacturer Part") "CR0603FA1001G") (field (name "Manufacturer") "LIZ(丽智电子)"))
      (libsource (lib "") (part "CR0603FA1001G_C126900"))
    )
    (comp (ref "R47")
      (value "470Ω")
      (fields (field (name "Manufacturer Part") "CR0603FA1001G") (field (name "Manufacturer") "LIZ(丽智电子)"))
      (libsource (lib "") (part "CR0603FA1001G_C126900"))
    )
    (comp (ref "R48")
      (value "470Ω")
      (fields (field (name "Manufacturer Part") "CR0603FA1001G") (field (name "Manufacturer") "LIZ(丽智电子)"))
      (libsource (lib "") (part "CR0603FA1001G_C126900"))
    )
    (comp (ref "R49")
      (value "10kΩ")
      (fields (field (name "Manufacturer Part") "TC33X-2-103E") (field (name "Manufacturer") "BOURNS"))
      (libsource (lib "") (part "TC33X-2-103E"))
    )
    (comp (ref "R50")
      (value "4.7kΩ[4]")
      (fields
        (field (name "Manufacturer Part") "0402WGF1002TCE")
        (field (name "Manufacturer") "UNI-ROYAL(厚声)")
      )
      (libsource (lib "") (part "0402WGF1002TCE"))
    )
    (comp (ref "R51")
      (value "4.7kΩ[4]")
      (fields
        (field (name "Manufacturer Part") "0402WGF1002TCE")
        (field (name "Manufacturer") "UNI-ROYAL(厚声)")
      )
      (libsource (lib "") (part "0402WGF1002TCE"))
    )
    (comp (ref "R52")
      (value "10kΩ[4]")
      (fields
        (field (name "Manufacturer Part") "0402WGF1002TCE")
        (field (name "Manufacturer") "UNI-ROYAL(厚声)")
      )
      (libsource (lib "") (part "0402WGF1002TCE"))
    )
    (comp (ref "R53")
      (value "10kΩ[4]")
      (fields
        (field (name "Manufacturer Part") "0402WGF1002TCE")
        (field (name "Manufacturer") "UNI-ROYAL(厚声)")
      )
      (libsource (lib "") (part "0402WGF1002TCE"))
    )
    (comp (ref "S1") (value "Debug") (libsource (lib "") (part "3PAD_SEL")))
    (comp (ref "SW1")
      (value "USB_BOOT")
      (fields
        (field (name "Manufacturer Part") "TS-1185EC-C-D-B")
        (field (name "Manufacturer") "XKB Connection(中国星坤)")
      )
      (libsource (lib "") (part "TS-1185EC-C-D-B"))
    )
    (comp (ref "SW2")
      (value "RUN")
      (fields
        (field (name "Manufacturer Part") "TS-1185EC-C-D-B")
        (field (name "Manufacturer") "XKB Connection(中国星坤)")
      )
      (libsource (lib "") (part "TS-1185EC-C-D-B"))
    )
    (comp (ref "SW3")
      (value "EC11L1525G01")
      (fields (field (name "Manufacturer") "ALPSALPINE(阿尔卑斯阿尔派)"))
      (libsource (lib "") (part "EC11L1525G01"))
    )
    (comp (ref "U1")
      (value "1N4148WS")
      (fields (field (name "Manufacturer") "Zhengxin(正芯)"))
      (libsource (lib "") (part "1N4148WS"))
    )
    (comp (ref "U2")
      (value "5V")
      (fields (field (name "Manufacturer Part") "2P,间距5.08mm,弹片压线升降式"))
      (libsource (lib "") (part "2P,间距5.08MM,弹片压线升降式_1"))
    )
    (comp (ref "U3")
      (value "KNX_OUT")
      (fields (field (name "Manufacturer Part") "2P,间距5.08mm,弹片压线升降式"))
      (libsource (lib "") (part "2P,间距5.08MM,弹片压线升降式"))
    )
    (comp (ref "U4")
      (value "KNX_IN")
      (fields (field (name "Manufacturer Part") "2P,间距5.08mm,弹片压线升降式"))
      (libsource (lib "") (part "2P,间距5.08MM,弹片压线升降式_1"))
    )
    (comp (ref "U5")
      (value "TLV1117-LV33")
      (fields (field (name "Manufacturer Part") "TLV1117LV33DCYR") (field (name "Manufacturer") "TI(德州仪器)"))
      (libsource (lib "") (part "TLV1117LV33DCYR"))
    )
    (comp (ref "U6")
      (value "1N4148WS")
      (fields (field (name "Manufacturer") "Zhengxin(正芯)"))
      (libsource (lib "") (part "1N4148WS"))
    )
    (comp (ref "U7")
      (value "STKNXTR")
      (fields (field (name "Manufacturer") "ST(意法半导体)"))
      (libsource (lib "") (part "STKNXTR"))
    )
    (comp (ref "U8")
      (value "1N4148WS")
      (fields (field (name "Manufacturer") "Zhengxin(正芯)"))
      (libsource (lib "") (part "1N4148WS_1"))
    )
    (comp (ref "U9")
      (value "68Ω(2W)")
      (fields
        (field (name "Manufacturer Part") "HoJLR2512-3W-3.5mR-1%")
        (field (name "Manufacturer") "Milliohm(毫欧)")
      )
      (libsource (lib "") (part "HOJLR2512-3W-3.5MR-1%"))
    )
    (comp (ref "U10") (value "KNX_VCC") (libsource (lib "") (part "Through hole")))
    (comp (ref "U11") (value "5V") (libsource (lib "") (part "Through hole")))
    (comp (ref "U12") (value "3.3V") (libsource (lib "") (part "Through hole")))
    (comp (ref "U13")
      (value "W25Q128JVSIM")
      (fields (field (name "Manufacturer") "WINBOND(华邦)"))
      (libsource (lib "") (part "W25Q128JVSIM"))
    )
    (comp (ref "U14")
      (value "T0")
      (fields
        (field (name "Manufacturer Part") "DB127V-5.08-3P-GN-S")
        (field (name "Manufacturer") "DIBO(地博电气)")
      )
      (libsource (lib "") (part "DB127V-5.08-3P-GN-S"))
    )
    (comp (ref "U15")
      (value "RP2040")
      (fields (field (name "Manufacturer") "Raspberry Pi(树莓派)"))
      (libsource (lib "") (part "RP2040"))
    )
    (comp (ref "U16")
      (value "T1")
      (fields
        (field (name "Manufacturer Part") "DB127V-5.08-3P-GN-S")
        (field (name "Manufacturer") "DIBO(地博电气)")
      )
      (libsource (lib "") (part "DB127V-5.08-3P-GN-S"))
    )
    (comp (ref "U17") (value "KNX_Rx") (libsource (lib "") (part "Through hole")))
    (comp (ref "U18") (value "KNX_Tx") (libsource (lib "") (part "Through hole")))
    (comp (ref "U19")
      (value "T2")
      (fields
        (field (name "Manufacturer Part") "DB127V-5.08-3P-GN-S")
        (field (name "Manufacturer") "DIBO(地博电气)")
      )
      (libsource (lib "") (part "DB127V-5.08-3P-GN-S"))
    )
    (comp (ref "U20")
      (value "INA219AID")
      (fields (field (name "Manufacturer") "TI(德州仪器)"))
      (libsource (lib "") (part "INA219AID"))
    )
    (comp (ref "U21")
      (value "T3")
      (fields
        (field (name "Manufacturer Part") "DB127V-5.08-3P-GN-S")
        (field (name "Manufacturer") "DIBO(地博电气)")
      )
      (libsource (lib "") (part "DB127V-5.08-3P-GN-S"))
    )
    (comp (ref "U22")
      (value "ATTINY3216")
      (fields
        (field (name "Manufacturer Part") "ATTINY1616-SN")
        (field (name "Manufacturer") "MICROCHIP(美国微芯)")
      )
      (libsource (lib "") (part "ATTINY1616-SN_C614136"))
    )
    (comp (ref "U23")
      (value "T4")
      (fields
        (field (name "Manufacturer Part") "DB127V-5.08-3P-GN-S")
        (field (name "Manufacturer") "DIBO(地博电气)")
      )
      (libsource (lib "") (part "DB127V-5.08-3P-GN-S"))
    )
    (comp (ref "U24")
      (value "PCF8574T/TR")
      (fields (field (name "Manufacturer") "HGSEMI(华冠)"))
      (libsource (lib "") (part "PCF8574T/TR"))
    )
    (comp (ref "U25")
      (value "T5")
      (fields
        (field (name "Manufacturer Part") "DB127V-5.08-3P-GN-S")
        (field (name "Manufacturer") "DIBO(地博电气)")
      )
      (libsource (lib "") (part "DB127V-5.08-3P-GN-S"))
    )
    (comp (ref "U26")
      (value "T6")
      (fields
        (field (name "Manufacturer Part") "DB127V-5.08-3P-GN-S")
        (field (name "Manufacturer") "DIBO(地博电气)")
      )
      (libsource (lib "") (part "DB127V-5.08-3P-GN-S"))
    )
    (comp (ref "U27")
      (value "T7")
      (fields
        (field (name "Manufacturer Part") "DB127V-5.08-3P-GN-S")
        (field (name "Manufacturer") "DIBO(地博电气)")
      )
      (libsource (lib "") (part "DB127V-5.08-3P-GN-S"))
    )
    (comp (ref "U28")
      (value "T8")
      (fields
        (field (name "Manufacturer Part") "DB127V-5.08-3P-GN-S")
        (field (name "Manufacturer") "DIBO(地博电气)")
      )
      (libsource (lib "") (part "DB127V-5.08-3P-GN-S"))
    )
    (comp (ref "U29")
      (value "TB6612FNG,C,8,EL")
      (fields (field (name "Manufacturer") "TOSHIBA(东芝)"))
      (libsource (lib "") (part "TB6612FNG,C,8,EL"))
    )
    (comp (ref "U30")
      (value "TB6612FNG,C,8,EL")
      (fields (field (name "Manufacturer") "TOSHIBA(东芝)"))
      (libsource (lib "") (part "TB6612FNG,C,8,EL"))
    )
    (comp (ref "U31")
      (value "TB6612FNG,C,8,EL")
      (fields (field (name "Manufacturer") "TOSHIBA(东芝)"))
      (libsource (lib "") (part "TB6612FNG,C,8,EL"))
    )
    (comp (ref "U32")
      (value "TB6612FNG,C,8,EL")
      (fields (field (name "Manufacturer") "TOSHIBA(东芝)"))
      (libsource (lib "") (part "TB6612FNG,C,8,EL"))
    )
    (comp (ref "U33")
      (value "M1")
      (fields (field (name "Manufacturer Part") "2P,间距5.08mm,弹片压线升降式"))
      (libsource (lib "") (part "2P,间距5.08MM,弹片压线升降式"))
    )
    (comp (ref "U34")
      (value "M2")
      (fields (field (name "Manufacturer Part") "2P,间距5.08mm,弹片压线升降式"))
      (libsource (lib "") (part "2P,间距5.08MM,弹片压线升降式"))
    )
    (comp (ref "U35")
      (value "M3")
      (fields (field (name "Manufacturer Part") "2P,间距5.08mm,弹片压线升降式"))
      (libsource (lib "") (part "2P,间距5.08MM,弹片压线升降式"))
    )
    (comp (ref "U36")
      (value "M4")
      (fields (field (name "Manufacturer Part") "2P,间距5.08mm,弹片压线升降式"))
      (libsource (lib "") (part "2P,间距5.08MM,弹片压线升降式"))
    )
    (comp (ref "U37")
      (value "M5")
      (fields (field (name "Manufacturer Part") "2P,间距5.08mm,弹片压线升降式"))
      (libsource (lib "") (part "2P,间距5.08MM,弹片压线升降式"))
    )
    (comp (ref "U38")
      (value "M6")
      (fields (field (name "Manufacturer Part") "2P,间距5.08mm,弹片压线升降式"))
      (libsource (lib "") (part "2P,间距5.08MM,弹片压线升降式"))
    )
    (comp (ref "U39")
      (value "M7")
      (fields (field (name "Manufacturer Part") "2P,间距5.08mm,弹片压线升降式"))
      (libsource (lib "") (part "2P,间距5.08MM,弹片压线升降式"))
    )
    (comp (ref "U40")
      (value "M8")
      (fields (field (name "Manufacturer Part") "2P,间距5.08mm,弹片压线升降式"))
      (libsource (lib "") (part "2P,间距5.08MM,弹片压线升降式"))
    )
    (comp (ref "U41") (value "T_Rx") (libsource (lib "") (part "Through hole")))
    (comp (ref "U42") (value "T_Tx") (libsource (lib "") (part "Through hole")))
    (comp (ref "USB1")
      (value "TYPE-C 16PIN 2MD(073)")
      (fields (field (name "Manufacturer") "SHOU HAN(首韩)"))
      (libsource (lib "") (part "TYPE-C 16PIN 2MD(073)"))
    )
    (comp (ref "X1")
      (value "12MHz")
      (fields (field (name "Manufacturer Part") "TAXM12M2QLFCDT1T") (field (name "Manufacturer") "YJX(雅晶鑫)"))
      (libsource (lib "") (part "SMD-5032_2P 12M 20pf 30ppm"))
    )
  )
  (nets
    (net (code "1") (name "1V1") (class "Default")
      (node (ref "C15") (pin "1") (pinfunction "1_1") (pintype "unspecified"))
      (node (ref "C16") (pin "1") (pinfunction "1_1") (pintype "unspecified"))
      (node (ref "C25") (pin "2") (pinfunction "2_2") (pintype "input"))
      (node (ref "U15") (pin "23") (pinfunction "DVDD_23") (pintype "bidirectional"))
      (node (ref "U15") (pin "45") (pinfunction "VREG_VOUT_45") (pintype "bidirectional"))
      (node (ref "U15") (pin "50") (pinfunction "DVDD_50") (pintype "bidirectional"))
    )
    (net (code "2") (name "3.3V") (class "Default")
      (node (ref "C17") (pin "1") (pinfunction "1_1") (pintype "unspecified"))
      (node (ref "C18") (pin "1") (pinfunction "1_1") (pintype "unspecified"))
      (node (ref "C19") (pin "1") (pinfunction "1_1") (pintype "unspecified"))
      (node (ref "C20") (pin "1") (pinfunction "1_1") (pintype "unspecified"))
      (node (ref "C21") (pin "1") (pinfunction "1_1") (pintype "unspecified"))
      (node (ref "C22") (pin "1") (pinfunction "1_1") (pintype "unspecified"))
      (node (ref "C23") (pin "1") (pinfunction "1_1") (pintype "unspecified"))
      (node (ref "C26") (pin "1") (pinfunction "1_1") (pintype "input"))
      (node (ref "C27") (pin "2") (pinfunction "2_2") (pintype "unspecified"))
      (node (ref "C3") (pin "2") (pinfunction "2_2") (pintype "input"))
      (node (ref "C33") (pin "2") (pinfunction "2_2") (pintype "input"))
      (node (ref "C34") (pin "2") (pinfunction "2_2") (pintype "unspecified"))
      (node (ref "C35") (pin "2") (pinfunction "2_2") (pintype "unspecified"))
      (node (ref "C36") (pin "1") (pinfunction "1_1") (pintype "unspecified"))
      (node (ref "C37") (pin "2") (pinfunction "2_2") (pintype "unspecified"))
      (node (ref "C46") (pin "1") (pinfunction "1_1") (pintype "input"))
      (node (ref "C47") (pin "1") (pinfunction "1_1") (pintype "input"))
      (node (ref "C48") (pin "1") (pinfunction "1_1") (pintype "unspecified"))
      (node (ref "C49") (pin "1") (pinfunction "1_1") (pintype "input"))
      (node (ref "C50") (pin "1") (pinfunction "1_1") (pintype "input"))
      (node (ref "C51") (pin "1") (pinfunction "1_1") (pintype "unspecified"))
      (node (ref "C52") (pin "1") (pinfunction "1_1") (pintype "unspecified"))
      (node (ref "C53") (pin "1") (pinfunction "1_1") (pintype "unspecified"))
      (node (ref "D3") (pin "1") (pinfunction "K_1") (pintype "unspecified"))
      (node (ref "LCD1") (pin "15") (pinfunction "BLA_15") (pintype "unspecified"))
      (node (ref "LCD1") (pin "2") (pinfunction "VDD_2") (pintype "unspecified"))
      (node (ref "R10") (pin "2") (pinfunction "2_2") (pintype "input"))
      (node (ref "R18") (pin "1") (pinfunction "1_1") (pintype "input"))
      (node (ref "R20") (pin "2") (pinfunction "2_2") (pintype "input"))
      (node (ref "R21") (pin "2") (pinfunction "2_2") (pintype "input"))
      (node (ref "R22") (pin "2") (pinfunction "2_2") (pintype "input"))
      (node (ref "R23") (pin "2") (pinfunction "2_2") (pintype "input"))
      (node (ref "R24") (pin "1") (pinfunction "1_1") (pintype "input"))
      (node (ref "R25") (pin "1") (pinfunction "1_1") (pintype "input"))
      (node (ref "R26") (pin "2") (pinfunction "2_2") (pintype "input"))
      (node (ref "R27") (pin "1") (pinfunction "1_1") (pintype "unspecified"))
      (node (ref "R28") (pin "2") (pinfunction "2_2") (pintype "input"))
      (node (ref "R29") (pin "1") (pinfunction "1_1") (pintype "input"))
      (node (ref "R31") (pin "2") (pinfunction "2_2") (pintype "input"))
      (node (ref "R32") (pin "2") (pinfunction "2_2") (pintype "input"))
      (node (ref "R33") (pin "2") (pinfunction "2_2") (pintype "input"))
      (node (ref "R35") (pin "2") (pinfunction "2_2") (pintype "input"))
      (node (ref "R36") (pin "2") (pinfunction "2_2") (pintype "input"))
      (node (ref "R38") (pin "2") (pinfunction "2_2") (pintype "input"))
      (node (ref "R43") (pin "2") (pinfunction "2_2") (pintype "input"))
      (node (ref "R44") (pin "2") (pinfunction "2_2") (pintype "input"))
      (node (ref "R50") (pin "2") (pinfunction "2_2") (pintype "input"))
      (node (ref "R51") (pin "2") (pinfunction "2_2") (pintype "input"))
      (node (ref "R52") (pin "2") (pinfunction "2_2") (pintype "input"))
      (node (ref "R53") (pin "2") (pinfunction "2_2") (pintype "input"))
      (node (ref "R6") (pin "1") (pinfunction "1_1") (pintype "input"))
      (node (ref "R8") (pin "1") (pinfunction "1_1") (pintype "input"))
      (node (ref "U12") (pin "1") (pinfunction "1_1") (pintype "unspecified"))
      (node (ref "U13") (pin "8") (pinfunction "VCC_8") (pintype "unspecified"))
      (node (ref "U14") (pin "3") (pinfunction "3_3") (pintype "unspecified"))
      (node (ref "U15") (pin "1") (pinfunction "IOVDD_1") (pintype "bidirectional"))
      (node (ref "U15") (pin "10") (pinfunction "IOVDD_10") (pintype "bidirectional"))
      (node (ref "U15") (pin "22") (pinfunction "IOVDD_22") (pintype "bidirectional"))
      (node (ref "U15") (pin "33") (pinfunction "IOVDD_33") (pintype "bidirectional"))
      (node (ref "U15") (pin "42") (pinfunction "IOVDD_42") (pintype "bidirectional"))
      (node (ref "U15") (pin "43") (pinfunction "ADC_AVDD_43") (pintype "bidirectional"))
      (node (ref "U15") (pin "44") (pinfunction "VREG_IN_44") (pintype "bidirectional"))
      (node (ref "U15") (pin "48") (pinfunction "USB_VDD_48") (pintype "bidirectional"))
      (node (ref "U15") (pin "49") (pinfunction "IOVDD_49") (pintype "bidirectional"))
      (node (ref "U16") (pin "3") (pinfunction "3_3") (pintype "unspecified"))
      (node (ref "U19") (pin "3") (pinfunction "3_3") (pintype "unspecified"))
      (node (ref "U20") (pin "5") (pinfunction "VS_5") (pintype "unspecified"))
      (node (ref "U21") (pin "3") (pinfunction "3_3") (pintype "unspecified"))
      (node (ref "U22") (pin "1") (pinfunction "VDD_1") (pintype "unspecified"))
      (node (ref "U23") (pin "3") (pinfunction "3_3") (pintype "unspecified"))
      (node (ref "U24") (pin "1") (pinfunction "A0_1") (pintype "unspecified"))
      (node (ref "U24") (pin "16") (pinfunction "VDD_16") (pintype "unspecified"))
      (node (ref "U24") (pin "2") (pinfunction "A1_2") (pintype "unspecified"))
      (node (ref "U24") (pin "3") (pinfunction "A2_3") (pintype "unspecified"))
      (node (ref "U25") (pin "3") (pinfunction "3_3") (pintype "unspecified"))
      (node (ref "U26") (pin "3") (pinfunction "3_3") (pintype "unspecified"))
      (node (ref "U27") (pin "3") (pinfunction "3_3") (pintype "unspecified"))
      (node (ref "U28") (pin "3") (pinfunction "3_3") (pintype "unspecified"))
      (node (ref "U29") (pin "19") (pinfunction "STBY_19") (pintype "unspecified"))
      (node (ref "U29") (pin "20") (pinfunction "VCC_20") (pintype "unspecified"))
      (node (ref "U30") (pin "19") (pinfunction "STBY_19") (pintype "unspecified"))
      (node (ref "U30") (pin "20") (pinfunction "VCC_20") (pintype "unspecified"))
      (node (ref "U31") (pin "19") (pinfunction "STBY_19") (pintype "unspecified"))
      (node (ref "U31") (pin "20") (pinfunction "VCC_20") (pintype "unspecified"))
      (node (ref "U32") (pin "19") (pinfunction "STBY_19") (pintype "unspecified"))
      (node (ref "U32") (pin "20") (pinfunction "VCC_20") (pintype "unspecified"))
      (node (ref "U5") (pin "2") (pinfunction "OUT_2") (pintype "passive"))
      (node (ref "U5") (pin "4") (pinfunction "OUT_4") (pintype "passive"))
    )
    (net (code "3") (name "5V") (class "Default")
      (node (ref "CN1") (pin "1") (pinfunction "1_1") (pintype "unspecified"))
      (node (ref "D1") (pin "2") (pinfunction "A_2") (pintype "unspecified"))
      (node (ref "D4") (pin "1") (pinfunction "K_1") (pintype "unspecified"))
      (node (ref "D5") (pin "1") (pinfunction "C_1") (pintype "unspecified"))
      (node (ref "F1") (pin "2") (pinfunction "2_2") (pintype "unspecified"))
      (node (ref "R7") (pin "2") (pinfunction "2_2") (pintype "input"))
      (node (ref "U11") (pin "1") (pinfunction "1_1") (pintype "unspecified"))
    )
    (net (code "4") (name "5V_") (class "Default")
      (node (ref "D6") (pin "1") (pinfunction "K_1") (pintype "unspecified"))
      (node (ref "F1") (pin "1") (pinfunction "1_1") (pintype "unspecified"))
      (node (ref "Q1") (pin "2") (pinfunction "S_2") (pintype "unspecified"))
      (node (ref "U2") (pin "1") (pinfunction "1_1") (pintype "unspecified"))
    )
    (net (code "5") (name "A") (class "Default")
      (node (ref "C29") (pin "2") (pinfunction "2_2") (pintype "input"))
      (node (ref "R24") (pin "2") (pinfunction "2_2") (pintype "input"))
      (node (ref "SW3") (pin "A") (pinfunction "A_A") (pintype "unspecified"))
      (node (ref "U15") (pin "8") (pinfunction "GPIO6_8") (pintype "bidirectional"))
    )
    (net (code "6") (name "B") (class "Default")
      (node (ref "C30") (pin "2") (pinfunction "2_2") (pintype "input"))
      (node (ref "R25") (pin "2") (pinfunction "2_2") (pintype "input"))
      (node (ref "SW3") (pin "B") (pinfunction "B_B") (pintype "unspecified"))
      (node (ref "U15") (pin "9") (pinfunction "GPIO7_9") (pintype "bidirectional"))
    )
    (net (code "7") (name "Button") (class "Default")
      (node (ref "C28") (pin "1") (pinfunction "1_1") (pintype "unspecified"))
      (node (ref "R18") (pin "2") (pinfunction "2_2") (pintype "input"))
      (node (ref "R19") (pin "1") (pinfunction "1_1") (pintype "input"))
      (node (ref "U15") (pin "4") (pinfunction "GPIO2_4") (pintype "bidirectional"))
    )
    (net (code "8") (name "CPH") (class "Default")
      (node (ref "R13") (pin "1") (pinfunction "1_1") (pintype "input"))
      (node (ref "U7") (pin "5") (pinfunction "CP_H_5") (pintype "unspecified"))
    )
    (net (code "9") (name "CPL") (class "Default")
      (node (ref "R11") (pin "1") (pinfunction "1_1") (pintype "input"))
      (node (ref "U7") (pin "6") (pinfunction "CP_L_6") (pintype "unspecified"))
    )
    (net (code "10") (name "CS") (class "Default")
      (node (ref "R52") (pin "1") (pinfunction "1_1") (pintype "input"))
      (node (ref "U15") (pin "32") (pinfunction "GPIO21_32") (pintype "bidirectional"))
      (node (ref "U22") (pin "2") (pinfunction "PA4_2") (pintype "unspecified"))
    )
    (net (code "11") (name "D+") (class "Default")
      (node (ref "R16") (pin "1") (pinfunction "1_1") (pintype "input"))
      (node (ref "USB1") (pin "6") (pinfunction "DP1_6") (pintype "unspecified"))
      (node (ref "USB1") (pin "8") (pinfunction "DP2_8") (pintype "unspecified"))
    )
    (net (code "12") (name "D-") (class "Default")
      (node (ref "R17") (pin "1") (pinfunction "1_1") (pintype "input"))
      (node (ref "USB1") (pin "5") (pinfunction "DN2_5") (pintype "unspecified"))
      (node (ref "USB1") (pin "7") (pinfunction "DN1_7") (pintype "unspecified"))
    )
    (net (code "13") (name "DCDC_FB") (class "Default")
      (node (ref "C13") (pin "2") (pinfunction "2_2") (pintype "input"))
      (node (ref "R14") (pin "1") (pinfunction "1_1") (pintype "input"))
      (node (ref "R15") (pin "2") (pinfunction "2_2") (pintype "input"))
      (node (ref "U7") (pin "18") (pinfunction "DCDC_FB_18") (pintype "unspecified"))
    )
    (net (code "14") (name "DCDC_LX") (class "Default")
      (node (ref "L1") (pin "1") (pinfunction "1_1") (pintype "unspecified"))
      (node (ref "U7") (pin "15") (pinfunction "DCDC_LX_15") (pintype "unspecified"))
    )
    (net (code "15") (name "DCDC_SS") (class "Default")
      (node (ref "C4") (pin "1") (pinfunction "1_1") (pintype "unspecified"))
      (node (ref "U7") (pin "17") (pinfunction "DCDC_SS_17") (pintype "unspecified"))
    )
    (net (code "16") (name "GND") (class "Default")
      (node (ref "C1") (pin "1") (pinfunction "1_1") (pintype "input"))
      (node (ref "C10") (pin "2") (pinfunction "2_2") (pintype "unspecified"))
      (node (ref "C11") (pin "2") (pinfunction "2_2") (pintype "unspecified"))
      (node (ref "C14") (pin "2") (pinfunction "2_2") (pintype "input"))
      (node (ref "C15") (pin "2") (pinfunction "2_2") (pintype "unspecified"))
      (node (ref "C16") (pin "2") (pinfunction "2_2") (pintype "unspecified"))
      (node (ref "C17") (pin "2") (pinfunction "2_2") (pintype "unspecified"))
      (node (ref "C18") (pin "2") (pinfunction "2_2") (pintype "unspecified"))
      (node (ref "C19") (pin "2") (pinfunction "2_2") (pintype "unspecified"))
      (node (ref "C2") (pin "1") (pinfunction "1_1") (pintype "input"))
      (node (ref "C20") (pin "2") (pinfunction "2_2") (pintype "unspecified"))
      (node (ref "C21") (pin "2") (pinfunction "2_2") (pintype "unspecified"))
      (node (ref "C22") (pin "2") (pinfunction "2_2") (pintype "unspecified"))
      (node (ref "C23") (pin "2") (pinfunction "2_2") (pintype "unspecified"))
      (node (ref "C24") (pin "2") (pinfunction "2_2") (pintype "input"))
      (node (ref "C25") (pin "1") (pinfunction "1_1") (pintype "input"))
      (node (ref "C26") (pin "2") (pinfunction "2_2") (pintype "input"))
      (node (ref "C27") (pin "1") (pinfunction "1_1") (pintype "unspecified"))
      (node (ref "C28") (pin "2") (pinfunction "2_2") (pintype "unspecified"))
      (node (ref "C29") (pin "1") (pinfunction "1_1") (pintype "input"))
      (node (ref "C3") (pin "1") (pinfunction "1_1") (pintype "input"))
      (node (ref "C30") (pin "1") (pinfunction "1_1") (pintype "input"))
      (node (ref "C31") (pin "1") (pinfunction "1_1") (pintype "input"))
      (node (ref "C32") (pin "1") (pinfunction "1_1") (pintype "input"))
      (node (ref "C34") (pin "1") (pinfunction "1_1") (pintype "unspecified"))
      (node (ref "C35") (pin "1") (pinfunction "1_1") (pintype "unspecified"))
      (node (ref "C36") (pin "2") (pinfunction "2_2") (pintype "unspecified"))
      (node (ref "C37") (pin "1") (pinfunction "1_1") (pintype "unspecified"))
      (node (ref "C38") (pin "1") (pinfunction "1_1") (pintype "unspecified"))
      (node (ref "C39") (pin "1") (pinfunction "1_1") (pintype "unspecified"))
      (node (ref "C4") (pin "2") (pinfunction "2_2") (pintype "unspecified"))
      (node (ref "C40") (pin "1") (pinfunction "1_1") (pintype "input"))
      (node (ref "C41") (pin "1") (pinfunction "1_1") (pintype "unspecified"))
      (node (ref "C42") (pin "1") (pinfunction "1_1") (pintype "unspecified"))
      (node (ref "C43") (pin "1") (pinfunction "1_1") (pintype "input"))
      (node (ref "C44") (pin "1") (pinfunction "1_1") (pintype "input"))
      (node (ref "C45") (pin "1") (pinfunction "1_1") (pintype "input"))
      (node (ref "C46") (pin "2") (pinfunction "2_2") (pintype "input"))
      (node (ref "C47") (pin "2") (pinfunction "2_2") (pintype "input"))
      (node (ref "C48") (pin "2") (pinfunction "2_2") (pintype "unspecified"))
      (node (ref "C49") (pin "2") (pinfunction "2_2") (pintype "input"))
      (node (ref "C5") (pin "1") (pinfunction "1_1") (pintype "input"))
      (node (ref "C50") (pin "2") (pinfunction "2_2") (pintype "input"))
      (node (ref "C51") (pin "2") (pinfunction "2_2") (pintype "unspecified"))
      (node (ref "C52") (pin "2") (pinfunction "2_2") (pintype "unspecified"))
      (node (ref "C53") (pin "2") (pinfunction "2_2") (pintype "unspecified"))
      (node (ref "C9") (pin "1") (pinfunction "1_1") (pintype "input"))
      (node (ref "CN1") (pin "5") (pinfunction "5_5") (pintype "unspecified"))
      (node (ref "CN1") (pin "6") (pinfunction "6_6") (pintype "unspecified"))
      (node (ref "D2") (pin "2") (pinfunction "2_2") (pintype "unspecified"))
      (node (ref "D3") (pin "2") (pinfunction "A_2") (pintype "unspecified"))
      (node (ref "D4") (pin "2") (pinfunction "A_2") (pintype "unspecified"))
      (node (ref "D5") (pin "2") (pinfunction "A_2") (pintype "unspecified"))
      (node (ref "LCD1") (pin "1") (pinfunction "VSS_1") (pintype "unspecified"))
      (node (ref "LCD1") (pin "10") (pinfunction "DB3_10") (pintype "unspecified"))
      (node (ref "LCD1") (pin "7") (pinfunction "DB0_7") (pintype "unspecified"))
      (node (ref "LCD1") (pin "8") (pinfunction "DB1_8") (pintype "unspecified"))
      (node (ref "LCD1") (pin "9") (pinfunction "DB2_9") (pintype "unspecified"))
      (node (ref "LED1") (pin "2") (pinfunction "-_2") (pintype "unspecified"))
      (node (ref "LED10") (pin "2") (pinfunction "-_2") (pintype "unspecified"))
      (node (ref "LED11") (pin "2") (pinfunction "-_2") (pintype "unspecified"))
      (node (ref "LED12") (pin "2") (pinfunction "-_2") (pintype "unspecified"))
      (node (ref "LED13") (pin "2") (pinfunction "-_2") (pintype "unspecified"))
      (node (ref "LED2") (pin "2") (pinfunction "-_2") (pintype "unspecified"))
      (node (ref "LED3") (pin "2") (pinfunction "-_2") (pintype "unspecified"))
      (node (ref "LED4") (pin "2") (pinfunction "-_2") (pintype "unspecified"))
      (node (ref "LED5") (pin "2") (pinfunction "-_2") (pintype "unspecified"))
      (node (ref "LED6") (pin "2") (pinfunction "-_2") (pintype "unspecified"))
      (node (ref "LED7") (pin "2") (pinfunction "-_2") (pintype "unspecified"))
      (node (ref "LED8") (pin "2") (pinfunction "-_2") (pintype "unspecified"))
      (node (ref "LED9") (pin "2") (pinfunction "-_2") (pintype "unspecified"))
      (node (ref "Q2") (pin "2") (pinfunction "2_2") (pintype "input"))
      (node (ref "R1") (pin "1") (pinfunction "1_1") (pintype "input"))
      (node (ref "R15") (pin "1") (pinfunction "1_1") (pintype "input"))
      (node (ref "R2") (pin "2") (pinfunction "2_2") (pintype "input"))
      (node (ref "R3") (pin "1") (pinfunction "1_1") (pintype "input"))
      (node (ref "R49") (pin "2") (pinfunction "2_2") (pintype "unspecified"))
      (node (ref "R5") (pin "2") (pinfunction "2_2") (pintype "input"))
      (node (ref "R9") (pin "1") (pinfunction "1_1") (pintype "input"))
      (node (ref "S1") (pin "2") (pinfunction "2_2") (pintype "unspecified"))
      (node (ref "SW1") (pin "2") (pinfunction "2_2") (pintype "unspecified"))
      (node (ref "SW2") (pin "2") (pinfunction "2_2") (pintype "unspecified"))
      (node (ref "SW3") (pin "C") (pinfunction "C_C") (pintype "unspecified"))
      (node (ref "SW3") (pin "E") (pinfunction "E_E") (pintype "unspecified"))
      (node (ref "U13") (pin "4") (pinfunction "GND_4") (pintype "unspecified"))
      (node (ref "U14") (pin "1") (pinfunction "1_1") (pintype "unspecified"))
      (node (ref "U15") (pin "19") (pinfunction "TESTEN_19") (pintype "unspecified"))
      (node (ref "U15") (pin "57") (pinfunction "GND_57") (pintype "bidirectional"))
      (node (ref "U16") (pin "1") (pinfunction "1_1") (pintype "unspecified"))
      (node (ref "U19") (pin "1") (pinfunction "1_1") (pintype "unspecified"))
      (node (ref "U2") (pin "2") (pinfunction "2_2") (pintype "unspecified"))
      (node (ref "U20") (pin "1") (pinfunction "A1_1") (pintype "unspecified"))
      (node (ref "U20") (pin "2") (pinfunction "A0_2") (pintype "unspecified"))
      (node (ref "U20") (pin "6") (pinfunction "GND_6") (pintype "unspecified"))
      (node (ref "U21") (pin "1") (pinfunction "1_1") (pintype "unspecified"))
      (node (ref "U22") (pin "20") (pinfunction "GND_20") (pintype "unspecified"))
      (node (ref "U23") (pin "1") (pinfunction "1_1") (pintype "unspecified"))
      (node (ref "U24") (pin "8") (pinfunction "VSS_8") (pintype "unspecified"))
      (node (ref "U25") (pin "1") (pinfunction "1_1") (pintype "unspecified"))
      (node (ref "U26") (pin "1") (pinfunction "1_1") (pintype "unspecified"))
      (node (ref "U27") (pin "1") (pinfunction "1_1") (pintype "unspecified"))
      (node (ref "U28") (pin "1") (pinfunction "1_1") (pintype "unspecified"))
      (node (ref "U29") (pin "10") (pinfunction "PGND2_10") (pintype "unspecified"))
      (node (ref "U29") (pin "18") (pinfunction "GND_18") (pintype "unspecified"))
      (node (ref "U29") (pin "3") (pinfunction "PGND1_3") (pintype "unspecified"))
      (node (ref "U29") (pin "4") (pinfunction "PGND1_4") (pintype "unspecified"))
      (node (ref "U29") (pin "9") (pinfunction "PGND2_9") (pintype "unspecified"))
      (node (ref "U3") (pin "2") (pinfunction "2_2") (pintype "unspecified"))
      (node (ref "U30") (pin "10") (pinfunction "PGND2_10") (pintype "unspecified"))
      (node (ref "U30") (pin "18") (pinfunction "GND_18") (pintype "unspecified"))
      (node (ref "U30") (pin "3") (pinfunction "PGND1_3") (pintype "unspecified"))
      (node (ref "U30") (pin "4") (pinfunction "PGND1_4") (pintype "unspecified"))
      (node (ref "U30") (pin "9") (pinfunction "PGND2_9") (pintype "unspecified"))
      (node (ref "U31") (pin "10") (pinfunction "PGND2_10") (pintype "unspecified"))
      (node (ref "U31") (pin "18") (pinfunction "GND_18") (pintype "unspecified"))
      (node (ref "U31") (pin "3") (pinfunction "PGND1_3") (pintype "unspecified"))
      (node (ref "U31") (pin "4") (pinfunction "PGND1_4") (pintype "unspecified"))
      (node (ref "U31") (pin "9") (pinfunction "PGND2_9") (pintype "unspecified"))
      (node (ref "U32") (pin "10") (pinfunction "PGND2_10") (pintype "unspecified"))
      (node (ref "U32") (pin "18") (pinfunction "GND_18") (pintype "unspecified"))
      (node (ref "U32") (pin "3") (pinfunction "PGND1_3") (pintype "unspecified"))
      (node (ref "U32") (pin "4") (pinfunction "PGND1_4") (pintype "unspecified"))
      (node (ref "U32") (pin "9") (pinfunction "PGND2_9") (pintype "unspecified"))
      (node (ref "U4") (pin "2") (pinfunction "2_2") (pintype "unspecified"))
      (node (ref "U5") (pin "1") (pinfunction "ADJ/GND_1") (pintype "passive"))
      (node (ref "U6") (pin "2") (pinfunction "A_2") (pintype "unspecified"))
      (node (ref "U7") (pin "12") (pinfunction "KNX_B_12") (pintype "unspecified"))
      (node (ref "U7") (pin "16") (pinfunction "DCDC_GND_16") (pintype "unspecified"))
      (node (ref "U7") (pin "22") (pinfunction "VCC_SEL_22") (pintype "unspecified"))
      (node (ref "U7") (pin "25") (pinfunction "EP_25") (pintype "unspecified"))
      (node (ref "U7") (pin "4") (pinfunction "KNX_B_4") (pintype "unspecified"))
      (node (ref "USB1") (pin "1") (pinfunction "GND_1") (pintype "unspecified"))
      (node (ref "USB1") (pin "12") (pinfunction "GND_12") (pintype "unspecified"))
      (node (ref "USB1") (pin "13") (pinfunction "SHELL_13") (pintype "unspecified"))
      (node (ref "USB1") (pin "14") (pinfunction "SHELL_14") (pintype "unspecified"))
    )
    (net (code "17") (name "IN_1") (class "Default")
      (node (ref "U15") (pin "29") (pinfunction "GPIO18_29") (pintype "bidirectional"))
      (node (ref "U29") (pin "17") (pinfunction "BIN1_17") (pintype "unspecified"))
      (node (ref "U29") (pin "21") (pinfunction "AIN1_21") (pintype "unspecified"))
      (node (ref "U30") (pin "17") (pinfunction "BIN1_17") (pintype "unspecified"))
      (node (ref "U30") (pin "21") (pinfunction "AIN1_21") (pintype "unspecified"))
      (node (ref "U31") (pin "17") (pinfunction "BIN1_17") (pintype "unspecified"))
      (node (ref "U31") (pin "21") (pinfunction "AIN1_21") (pintype "unspecified"))
      (node (ref "U32") (pin "17") (pinfunction "BIN1_17") (pintype "unspecified"))
      (node (ref "U32") (pin "21") (pinfunction "AIN1_21") (pintype "unspecified"))
    )
    (net (code "18") (name "IN_2") (class "Default")
      (node (ref "U15") (pin "30") (pinfunction "GPIO19_30") (pintype "bidirectional"))
      (node (ref "U29") (pin "16") (pinfunction "BIN2_16") (pintype "unspecified"))
      (node (ref "U29") (pin "22") (pinfunction "AIN2_22") (pintype "unspecified"))
      (node (ref "U30") (pin "16") (pinfunction "BIN2_16") (pintype "unspecified"))
      (node (ref "U30") (pin "22") (pinfunction "AIN2_22") (pintype "unspecified"))
      (node (ref "U31") (pin "16") (pinfunction "BIN2_16") (pintype "unspecified"))
      (node (ref "U31") (pin "22") (pinfunction "AIN2_22") (pintype "unspecified"))
      (node (ref "U32") (pin "16") (pinfunction "BIN2_16") (pintype "unspecified"))
      (node (ref "U32") (pin "22") (pinfunction "AIN2_22") (pintype "unspecified"))
    )
    (net (code "19") (name "KNC_AC") (class "Default")
      (node (ref "C6") (pin "2") (pinfunction "2_2") (pintype "input"))
      (node (ref "U6") (pin "1") (pinfunction "K_1") (pintype "unspecified"))
      (node (ref "U7") (pin "2") (pinfunction "KNX_AC_2") (pintype "unspecified"))
    )
    (net (code "20") (name "KNX+") (class "Default")
      (node (ref "C12") (pin "2") (pinfunction "2_2") (pintype "unspecified"))
      (node (ref "D2") (pin "1") (pinfunction "1_1") (pintype "unspecified"))
      (node (ref "R2") (pin "1") (pinfunction "1_1") (pintype "input"))
      (node (ref "U1") (pin "2") (pinfunction "A_2") (pintype "unspecified"))
      (node (ref "U3") (pin "1") (pinfunction "1_1") (pintype "unspecified"))
      (node (ref "U4") (pin "1") (pinfunction "1_1") (pintype "unspecified"))
    )
    (net (code "21") (name "KNX_A") (class "Default")
      (node (ref "C6") (pin "1") (pinfunction "1_1") (pintype "input"))
      (node (ref "C8") (pin "1") (pinfunction "1_1") (pintype "input"))
      (node (ref "U1") (pin "1") (pinfunction "K_1") (pintype "unspecified"))
      (node (ref "U7") (pin "11") (pinfunction "KNX_A_11") (pintype "unspecified"))
      (node (ref "U9") (pin "2") (pinfunction "2_2") (pintype "unspecified"))
    )
    (net (code "22") (name "KNX_OK") (class "Default")
      (node (ref "U15") (pin "31") (pinfunction "GPIO20_31") (pintype "bidirectional"))
      (node (ref "U7") (pin "21") (pinfunction "KNX_OK_21") (pintype "unspecified"))
    )
    (net (code "23") (name "KNX_Rx") (class "Default")
      (node (ref "JMP1") (pin "2") (pinfunction "2_2") (pintype "unspecified"))
      (node (ref "R21") (pin "1") (pinfunction "1_1") (pintype "input"))
      (node (ref "U17") (pin "1") (pinfunction "1_1") (pintype "unspecified"))
      (node (ref "U7") (pin "23") (pinfunction "KNX_RX_23") (pintype "unspecified"))
    )
    (net (code "24") (name "KNX_Rx'") (class "Default")
      (node (ref "JMP1") (pin "1") (pinfunction "1_1") (pintype "unspecified"))
      (node (ref "U15") (pin "3") (pinfunction "GPIO1_3") (pintype "bidirectional"))
    )
    (net (code "25") (name "KNX_Tx") (class "Default")
      (node (ref "JMP2") (pin "2") (pinfunction "2_2") (pintype "unspecified"))
      (node (ref "R20") (pin "1") (pinfunction "1_1") (pintype "input"))
      (node (ref "U18") (pin "1") (pinfunction "1_1") (pintype "unspecified"))
      (node (ref "U7") (pin "24") (pinfunction "KNX_TX_24") (pintype "unspecified"))
    )
    (net (code "26") (name "KNX_Tx'") (class "Default")
      (node (ref "JMP2") (pin "1") (pinfunction "1_1") (pintype "unspecified"))
      (node (ref "U15") (pin "2") (pinfunction "GPIO0_2") (pintype "bidirectional"))
    )
    (net (code "27") (name "KNX_VCC") (class "Default")
      (node (ref "C13") (pin "1") (pinfunction "1_1") (pintype "input"))
      (node (ref "C24") (pin "1") (pinfunction "1_1") (pintype "input"))
      (node (ref "L1") (pin "2") (pinfunction "2_2") (pintype "unspecified"))
      (node (ref "Q1") (pin "3") (pinfunction "D_3") (pintype "unspecified"))
      (node (ref "R14") (pin "2") (pinfunction "2_2") (pintype "input"))
      (node (ref "R9") (pin "2") (pinfunction "2_2") (pintype "input"))
      (node (ref "U10") (pin "1") (pinfunction "1_1") (pintype "unspecified"))
    )
    (net (code "28") (name "LED") (class "Default")
      (node (ref "R34") (pin "2") (pinfunction "2_2") (pintype "input"))
      (node (ref "U15") (pin "37") (pinfunction "GPIO25_37") (pintype "bidirectional"))
    )
    (net (code "29") (name "LED_2") (class "Default")
      (node (ref "R37") (pin "2") (pinfunction "2_2") (pintype "input"))
      (node (ref "U22") (pin "15") (pinfunction "PC3_15") (pintype "unspecified"))
    )
    (net (code "30") (name "M1+") (class "Default")
      (node (ref "U29") (pin "1") (pinfunction "AO1_1") (pintype "unspecified"))
      (node (ref "U29") (pin "2") (pinfunction "AO1_2") (pintype "unspecified"))
      (node (ref "U33") (pin "1") (pinfunction "1_1") (pintype "unspecified"))
    )
    (net (code "31") (name "M1-") (class "Default")
      (node (ref "U29") (pin "5") (pinfunction "AO2_5") (pintype "unspecified"))
      (node (ref "U29") (pin "6") (pinfunction "AO2_6") (pintype "unspecified"))
      (node (ref "U33") (pin "2") (pinfunction "2_2") (pintype "unspecified"))
    )
    (net (code "32") (name "M1_EN") (class "Default")
      (node (ref "R42") (pin "2") (pinfunction "2_2") (pintype "input"))
      (node (ref "U15") (pin "13") (pinfunction "GPIO10_13") (pintype "bidirectional"))
      (node (ref "U29") (pin "23") (pinfunction "PWMA_23") (pintype "unspecified"))
    )
    (net (code "33") (name "M2+") (class "Default")
      (node (ref "U29") (pin "11") (pinfunction "BO1_11") (pintype "unspecified"))
      (node (ref "U29") (pin "12") (pinfunction "BO1_12") (pintype "unspecified"))
      (node (ref "U34") (pin "1") (pinfunction "1_1") (pintype "unspecified"))
    )
    (net (code "34") (name "M2-") (class "Default")
      (node (ref "U29") (pin "7") (pinfunction "BO2_7") (pintype "unspecified"))
      (node (ref "U29") (pin "8") (pinfunction "BO2_8") (pintype "unspecified"))
      (node (ref "U34") (pin "2") (pinfunction "2_2") (pintype "unspecified"))
    )
    (net (code "35") (name "M2_EN") (class "Default")
      (node (ref "R48") (pin "2") (pinfunction "2_2") (pintype "input"))
      (node (ref "U15") (pin "14") (pinfunction "GPIO11_14") (pintype "bidirectional"))
      (node (ref "U29") (pin "15") (pinfunction "PWMB_15") (pintype "unspecified"))
    )
    (net (code "36") (name "M3+") (class "Default")
      (node (ref "U31") (pin "1") (pinfunction "AO1_1") (pintype "unspecified"))
      (node (ref "U31") (pin "2") (pinfunction "AO1_2") (pintype "unspecified"))
      (node (ref "U35") (pin "1") (pinfunction "1_1") (pintype "unspecified"))
    )
    (net (code "37") (name "M3-") (class "Default")
      (node (ref "U31") (pin "5") (pinfunction "AO2_5") (pintype "unspecified"))
      (node (ref "U31") (pin "6") (pinfunction "AO2_6") (pintype "unspecified"))
      (node (ref "U35") (pin "2") (pinfunction "2_2") (pintype "unspecified"))
    )
    (net (code "38") (name "M3_EN") (class "Default")
      (node (ref "R41") (pin "2") (pinfunction "2_2") (pintype "input"))
      (node (ref "U15") (pin "15") (pinfunction "GPIO12_15") (pintype "bidirectional"))
      (node (ref "U31") (pin "23") (pinfunction "PWMA_23") (pintype "unspecified"))
    )
    (net (code "39") (name "M4+") (class "Default")
      (node (ref "U31") (pin "11") (pinfunction "BO1_11") (pintype "unspecified"))
      (node (ref "U31") (pin "12") (pinfunction "BO1_12") (pintype "unspecified"))
      (node (ref "U36") (pin "1") (pinfunction "1_1") (pintype "unspecified"))
    )
    (net (code "40") (name "M4-") (class "Default")
      (node (ref "U31") (pin "7") (pinfunction "BO2_7") (pintype "unspecified"))
      (node (ref "U31") (pin "8") (pinfunction "BO2_8") (pintype "unspecified"))
      (node (ref "U36") (pin "2") (pinfunction "2_2") (pintype "unspecified"))
    )
    (net (code "41") (name "M4_EN") (class "Default")
      (node (ref "R47") (pin "2") (pinfunction "2_2") (pintype "input"))
      (node (ref "U15") (pin "16") (pinfunction "GPIO13_16") (pintype "bidirectional"))
      (node (ref "U31") (pin "15") (pinfunction "PWMB_15") (pintype "unspecified"))
    )
    (net (code "42") (name "M5+") (class "Default")
      (node (ref "U32") (pin "1") (pinfunction "AO1_1") (pintype "unspecified"))
      (node (ref "U32") (pin "2") (pinfunction "AO1_2") (pintype "unspecified"))
      (node (ref "U37") (pin "1") (pinfunction "1_1") (pintype "unspecified"))
    )
    (net (code "43") (name "M5-") (class "Default")
      (node (ref "U32") (pin "5") (pinfunction "AO2_5") (pintype "unspecified"))
      (node (ref "U32") (pin "6") (pinfunction "AO2_6") (pintype "unspecified"))
      (node (ref "U37") (pin "2") (pinfunction "2_2") (pintype "unspecified"))
    )
    (net (code "44") (name "M5_EN") (class "Default")
      (node (ref "R39") (pin "2") (pinfunction "2_2") (pintype "input"))
      (node (ref "U15") (pin "17") (pinfunction "GPIO14_17") (pintype "bidirectional"))
      (node (ref "U32") (pin "23") (pinfunction "PWMA_23") (pintype "unspecified"))
    )
    (net (code "45") (name "M6+") (class "Default")
      (node (ref "U32") (pin "11") (pinfunction "BO1_11") (pintype "unspecified"))
      (node (ref "U32") (pin "12") (pinfunction "BO1_12") (pintype "unspecified"))
      (node (ref "U38") (pin "1") (pinfunction "1_1") (pintype "unspecified"))
    )
    (net (code "46") (name "M6-") (class "Default")
      (node (ref "U32") (pin "7") (pinfunction "BO2_7") (pintype "unspecified"))
      (node (ref "U32") (pin "8") (pinfunction "BO2_8") (pintype "unspecified"))
      (node (ref "U38") (pin "2") (pinfunction "2_2") (pintype "unspecified"))
    )
    (net (code "47") (name "M6_EN") (class "Default")
      (node (ref "R45") (pin "2") (pinfunction "2_2") (pintype "input"))
      (node (ref "U15") (pin "18") (pinfunction "GPIO15_18") (pintype "bidirectional"))
      (node (ref "U32") (pin "15") (pinfunction "PWMB_15") (pintype "unspecified"))
    )
    (net (code "48") (name "M7+") (class "Default")
      (node (ref "U30") (pin "1") (pinfunction "AO1_1") (pintype "unspecified"))
      (node (ref "U30") (pin "2") (pinfunction "AO1_2") (pintype "unspecified"))
      (node (ref "U39") (pin "1") (pinfunction "1_1") (pintype "unspecified"))
    )
    (net (code "49") (name "M7-") (class "Default")
      (node (ref "U30") (pin "5") (pinfunction "AO2_5") (pintype "unspecified"))
      (node (ref "U30") (pin "6") (pinfunction "AO2_6") (pintype "unspecified"))
      (node (ref "U39") (pin "2") (pinfunction "2_2") (pintype "unspecified"))
    )
    (net (code "50") (name "M7_EN") (class "Default")
      (node (ref "R40") (pin "2") (pinfunction "2_2") (pintype "input"))
      (node (ref "U15") (pin "27") (pinfunction "GPIO16_27") (pintype "bidirectional"))
      (node (ref "U30") (pin "23") (pinfunction "PWMA_23") (pintype "unspecified"))
    )
    (net (code "51") (name "M8+") (class "Default")
      (node (ref "U30") (pin "11") (pinfunction "BO1_11") (pintype "unspecified"))
      (node (ref "U30") (pin "12") (pinfunction "BO1_12") (pintype "unspecified"))
      (node (ref "U40") (pin "1") (pinfunction "1_1") (pintype "unspecified"))
    )
    (net (code "52") (name "M8-") (class "Default")
      (node (ref "U30") (pin "7") (pinfunction "BO2_7") (pintype "unspecified"))
      (node (ref "U30") (pin "8") (pinfunction "BO2_8") (pintype "unspecified"))
      (node (ref "U40") (pin "2") (pinfunction "2_2") (pintype "unspecified"))
    )
    (net (code "53") (name "M8_EN") (class "Default")
      (node (ref "R46") (pin "2") (pinfunction "2_2") (pintype "input"))
      (node (ref "U15") (pin "28") (pinfunction "GPIO17_28") (pintype "bidirectional"))
      (node (ref "U30") (pin "15") (pinfunction "PWMB_15") (pintype "unspecified"))
    )
    (net (code "54") (name "M_VCC") (class "Default")
      (node (ref "C33") (pin "1") (pinfunction "1_1") (pintype "input"))
      (node (ref "C38") (pin "2") (pinfunction "2_2") (pintype "unspecified"))
      (node (ref "C39") (pin "2") (pinfunction "2_2") (pintype "unspecified"))
      (node (ref "C40") (pin "2") (pinfunction "2_2") (pintype "input"))
      (node (ref "C41") (pin "2") (pinfunction "2_2") (pintype "unspecified"))
      (node (ref "C42") (pin "2") (pinfunction "2_2") (pintype "unspecified"))
      (node (ref "C43") (pin "2") (pinfunction "2_2") (pintype "input"))
      (node (ref "C44") (pin "2") (pinfunction "2_2") (pintype "input"))
      (node (ref "C45") (pin "2") (pinfunction "2_2") (pintype "input"))
      (node (ref "R27") (pin "2") (pinfunction "2_2") (pintype "unspecified"))
      (node (ref "R30") (pin "1") (pinfunction "1_1") (pintype "input"))
      (node (ref "U29") (pin "13") (pinfunction "VM2_13") (pintype "unspecified"))
      (node (ref "U29") (pin "14") (pinfunction "VM3_14") (pintype "unspecified"))
      (node (ref "U29") (pin "24") (pinfunction "VM1_24") (pintype "unspecified"))
      (node (ref "U30") (pin "13") (pinfunction "VM2_13") (pintype "unspecified"))
      (node (ref "U30") (pin "14") (pinfunction "VM3_14") (pintype "unspecified"))
      (node (ref "U30") (pin "24") (pinfunction "VM1_24") (pintype "unspecified"))
      (node (ref "U31") (pin "13") (pinfunction "VM2_13") (pintype "unspecified"))
      (node (ref "U31") (pin "14") (pinfunction "VM3_14") (pintype "unspecified"))
      (node (ref "U31") (pin "24") (pinfunction "VM1_24") (pintype "unspecified"))
      (node (ref "U32") (pin "13") (pinfunction "VM2_13") (pintype "unspecified"))
      (node (ref "U32") (pin "14") (pinfunction "VM3_14") (pintype "unspecified"))
      (node (ref "U32") (pin "24") (pinfunction "VM1_24") (pintype "unspecified"))
    )
    (net (code "55") (name "Net-(C10-Pad1)") (class "Default")
      (node (ref "C10") (pin "1") (pinfunction "1_1") (pintype "unspecified"))
      (node (ref "R11") (pin "2") (pinfunction "2_2") (pintype "input"))
    )
    (net (code "56") (name "Net-(C12-Pad1)") (class "Default")
      (node (ref "C12") (pin "1") (pinfunction "1_1") (pintype "unspecified"))
      (node (ref "R13") (pin "2") (pinfunction "2_2") (pintype "input"))
    )
    (net (code "57") (name "Net-(D1-K)") (class "Default")
      (node (ref "C2") (pin "2") (pinfunction "2_2") (pintype "input"))
      (node (ref "D1") (pin "1") (pinfunction "K_1") (pintype "unspecified"))
      (node (ref "U5") (pin "3") (pinfunction "IN_3") (pintype "passive"))
    )
    (net (code "58") (name "Net-(LCD1-BLK)") (class "Default")
      (node (ref "LCD1") (pin "16") (pinfunction "BLK_16") (pintype "unspecified"))
      (node (ref "Q2") (pin "3") (pinfunction "3_3") (pintype "input"))
    )
    (net (code "59") (name "Net-(LCD1-DB4)") (class "Default")
      (node (ref "LCD1") (pin "11") (pinfunction "DB4_11") (pintype "unspecified"))
      (node (ref "U24") (pin "9") (pinfunction "P4_9") (pintype "unspecified"))
    )
    (net (code "60") (name "Net-(LCD1-DB5)") (class "Default")
      (node (ref "LCD1") (pin "12") (pinfunction "DB5_12") (pintype "unspecified"))
      (node (ref "U24") (pin "10") (pinfunction "P5_10") (pintype "unspecified"))
    )
    (net (code "61") (name "Net-(LCD1-DB6)") (class "Default")
      (node (ref "LCD1") (pin "13") (pinfunction "DB6_13") (pintype "unspecified"))
      (node (ref "U24") (pin "11") (pinfunction "P6_11") (pintype "unspecified"))
    )
    (net (code "62") (name "Net-(LCD1-DB7)") (class "Default")
      (node (ref "LCD1") (pin "14") (pinfunction "DB7_14") (pintype "unspecified"))
      (node (ref "U24") (pin "12") (pinfunction "P7_12") (pintype "unspecified"))
    )
    (net (code "63") (name "Net-(LCD1-E)") (class "Default")
      (node (ref "LCD1") (pin "6") (pinfunction "E_6") (pintype "unspecified"))
      (node (ref "U24") (pin "6") (pinfunction "P2_6") (pintype "unspecified"))
    )
    (net (code "64") (name "Net-(LCD1-RS)") (class "Default")
      (node (ref "LCD1") (pin "4") (pinfunction "RS_4") (pintype "unspecified"))
      (node (ref "U24") (pin "4") (pinfunction "P0_4") (pintype "unspecified"))
    )
    (net (code "65") (name "Net-(LCD1-RW)") (class "Default")
      (node (ref "LCD1") (pin "5") (pinfunction "RW_5") (pintype "unspecified"))
      (node (ref "U24") (pin "5") (pinfunction "P1_5") (pintype "unspecified"))
    )
    (net (code "66") (name "Net-(LCD1-V0)") (class "Default")
      (node (ref "LCD1") (pin "3") (pinfunction "V0_3") (pintype "unspecified"))
      (node (ref "R49") (pin "1") (pinfunction "1_1") (pintype "unspecified"))
    )
    (net (code "67") (name "Net-(LED1-+)") (class "Default")
      (node (ref "LED1") (pin "1") (pinfunction "+_1") (pintype "unspecified"))
      (node (ref "R4") (pin "1") (pinfunction "1_1") (pintype "input"))
    )
    (net (code "68") (name "Net-(LED2-+)") (class "Default")
      (node (ref "LED2") (pin "1") (pinfunction "+_1") (pintype "unspecified"))
      (node (ref "R7") (pin "1") (pinfunction "1_1") (pintype "input"))
    )
    (net (code "69") (name "Net-(LED3-+)") (class "Default")
      (node (ref "LED3") (pin "1") (pinfunction "+_1") (pintype "unspecified"))
      (node (ref "R10") (pin "1") (pinfunction "1_1") (pintype "input"))
    )
    (net (code "70") (name "Net-(LED4-+)") (class "Default")
      (node (ref "LED4") (pin "1") (pinfunction "+_1") (pintype "unspecified"))
      (node (ref "R34") (pin "1") (pinfunction "1_1") (pintype "input"))
    )
    (net (code "71") (name "Net-(LED5-+)") (class "Default")
      (node (ref "LED5") (pin "1") (pinfunction "+_1") (pintype "unspecified"))
      (node (ref "R37") (pin "1") (pinfunction "1_1") (pintype "input"))
    )
    (net (code "72") (name "Net-(LED6-+)") (class "Default")
      (node (ref "LED6") (pin "1") (pinfunction "+_1") (pintype "unspecified"))
      (node (ref "R39") (pin "1") (pinfunction "1_1") (pintype "input"))
    )
    (net (code "73") (name "Net-(LED7-+)") (class "Default")
      (node (ref "LED7") (pin "1") (pinfunction "+_1") (pintype "unspecified"))
      (node (ref "R40") (pin "1") (pinfunction "1_1") (pintype "input"))
    )
    (net (code "74") (name "Net-(LED8-+)") (class "Default")
      (node (ref "LED8") (pin "1") (pinfunction "+_1") (pintype "unspecified"))
      (node (ref "R41") (pin "1") (pinfunction "1_1") (pintype "input"))
    )
    (net (code "75") (name "Net-(LED9-+)") (class "Default")
      (node (ref "LED9") (pin "1") (pinfunction "+_1") (pintype "unspecified"))
      (node (ref "R42") (pin "1") (pinfunction "1_1") (pintype "input"))
    )
    (net (code "76") (name "Net-(LED10-+)") (class "Default")
      (node (ref "LED10") (pin "1") (pinfunction "+_1") (pintype "unspecified"))
      (node (ref "R45") (pin "1") (pinfunction "1_1") (pintype "input"))
    )
    (net (code "77") (name "Net-(LED11-+)") (class "Default")
      (node (ref "LED11") (pin "1") (pinfunction "+_1") (pintype "unspecified"))
      (node (ref "R46") (pin "1") (pinfunction "1_1") (pintype "input"))
    )
    (net (code "78") (name "Net-(LED12-+)") (class "Default")
      (node (ref "LED12") (pin "1") (pinfunction "+_1") (pintype "unspecified"))
      (node (ref "R47") (pin "1") (pinfunction "1_1") (pintype "input"))
    )
    (net (code "79") (name "Net-(LED13-+)") (class "Default")
      (node (ref "LED13") (pin "1") (pinfunction "+_1") (pintype "unspecified"))
      (node (ref "R48") (pin "1") (pinfunction "1_1") (pintype "input"))
    )
    (net (code "80") (name "Net-(R12-Pad2)") (class "Default")
      (node (ref "R12") (pin "2") (pinfunction "2_2") (pintype "input"))
      (node (ref "SW1") (pin "1") (pinfunction "1_1") (pintype "unspecified"))
    )
    (net (code "81") (name "Net-(R19-Pad2)") (class "Default")
      (node (ref "R19") (pin "2") (pinfunction "2_2") (pintype "input"))
      (node (ref "SW3") (pin "D") (pinfunction "D_D") (pintype "unspecified"))
    )
    (net (code "82") (name "Net-(U7-VREF)") (class "Default")
      (node (ref "C5") (pin "2") (pinfunction "2_2") (pintype "input"))
      (node (ref "U7") (pin "8") (pinfunction "VREF_8") (pintype "unspecified"))
    )
    (net (code "83") (name "Net-(U15-USB_DM)") (class "Default")
      (node (ref "R17") (pin "2") (pinfunction "2_2") (pintype "input"))
      (node (ref "U15") (pin "46") (pinfunction "USB_DM_46") (pintype "bidirectional"))
    )
    (net (code "84") (name "Net-(U15-USB_DP)") (class "Default")
      (node (ref "R16") (pin "2") (pinfunction "2_2") (pintype "input"))
      (node (ref "U15") (pin "47") (pinfunction "USB_DP_47") (pintype "bidirectional"))
    )
    (net (code "85") (name "Net-(U15-XIN)") (class "Default")
      (node (ref "C31") (pin "2") (pinfunction "2_2") (pintype "input"))
      (node (ref "U15") (pin "20") (pinfunction "XIN_20") (pintype "input"))
      (node (ref "X1") (pin "1") (pinfunction "OSC1_1") (pintype "input"))
    )
    (net (code "86") (name "Net-(U15-XOUT)") (class "Default")
      (node (ref "C32") (pin "2") (pinfunction "2_2") (pintype "input"))
      (node (ref "U15") (pin "21") (pinfunction "XOUT_21") (pintype "unspecified"))
      (node (ref "X1") (pin "2") (pinfunction "OSC2_2") (pintype "input"))
    )
    (net (code "87") (name "Net-(U20-IN+)") (class "Default")
      (node (ref "R29") (pin "2") (pinfunction "2_2") (pintype "input"))
      (node (ref "U20") (pin "8") (pinfunction "IN+_8") (pintype "unspecified"))
    )
    (net (code "88") (name "Net-(U20-IN-)") (class "Default")
      (node (ref "R30") (pin "2") (pinfunction "2_2") (pintype "input"))
      (node (ref "U20") (pin "7") (pinfunction "IN-_7") (pintype "unspecified"))
    )
    (net (code "89") (name "Net-(U24-P3)") (class "Default")
      (node (ref "Q2") (pin "1") (pinfunction "1_1") (pintype "input"))
      (node (ref "R43") (pin "1") (pinfunction "1_1") (pintype "input"))
      (node (ref "U24") (pin "7") (pinfunction "P3_7") (pintype "unspecified"))
    )
    (net (code "90") (name "Net-(USB1-CC1)") (class "Default")
      (node (ref "R3") (pin "2") (pinfunction "2_2") (pintype "input"))
      (node (ref "USB1") (pin "4") (pinfunction "CC1_4") (pintype "unspecified"))
    )
    (net (code "91") (name "Net-(USB1-CC2)") (class "Default")
      (node (ref "R1") (pin "2") (pinfunction "2_2") (pintype "input"))
      (node (ref "USB1") (pin "10") (pinfunction "CC2_10") (pintype "unspecified"))
    )
    (net (code "92") (name "QSPI_SCK") (class "Default")
      (node (ref "U13") (pin "6") (pinfunction "CLK_6") (pintype "unspecified"))
      (node (ref "U15") (pin "52") (pinfunction "QSPI_SCLK_52") (pintype "output"))
    )
    (net (code "93") (name "QSPI_SD0") (class "Default")
      (node (ref "U13") (pin "5") (pinfunction "DI(IO0)_5") (pintype "unspecified"))
      (node (ref "U15") (pin "53") (pinfunction "QSPI_SD0_53") (pintype "bidirectional"))
    )
    (net (code "94") (name "QSPI_SD1") (class "Default")
      (node (ref "U13") (pin "2") (pinfunction "DO(IO1)_2") (pintype "unspecified"))
      (node (ref "U15") (pin "55") (pinfunction "QSPI_SD1_55") (pintype "bidirectional"))
    )
    (net (code "95") (name "QSPI_SD2") (class "Default")
      (node (ref "U13") (pin "3") (pinfunction "/WP(IO2)_3") (pintype "unspecified"))
      (node (ref "U15") (pin "54") (pinfunction "QSPI_SD2_54") (pintype "bidirectional"))
    )
    (net (code "96") (name "QSPI_SD3") (class "Default")
      (node (ref "U13") (pin "7") (pinfunction "/HOLDor/RESET(IO3)_7") (pintype "unspecified"))
      (node (ref "U15") (pin "51") (pinfunction "QSPI_SD3_51") (pintype "bidirectional"))
    )
    (net (code "97") (name "QSPI_SS") (class "Default")
      (node (ref "R12") (pin "1") (pinfunction "1_1") (pintype "input"))
      (node (ref "R8") (pin "2") (pinfunction "2_2") (pintype "input"))
      (node (ref "U13") (pin "1") (pinfunction "/CS_1") (pintype "unspecified"))
      (node (ref "U15") (pin "56") (pinfunction "QSPI_SS_56") (pintype "bidirectional"))
    )
    (net (code "98") (name "R68") (class "Default")
      (node (ref "U7") (pin "3") (pinfunction "R68_3") (pintype "unspecified"))
      (node (ref "U9") (pin "1") (pinfunction "1_1") (pintype "unspecified"))
    )
    (net (code "99") (name "RUN") (class "Default")
      (node (ref "R6") (pin "2") (pinfunction "2_2") (pintype "input"))
      (node (ref "SW2") (pin "1") (pinfunction "1_1") (pintype "unspecified"))
      (node (ref "U15") (pin "26") (pinfunction "RUN_26") (pintype "input"))
    )
    (net (code "100") (name "RxD") (class "Default")
      (node (ref "CN1") (pin "2") (pinfunction "2_2") (pintype "unspecified"))
      (node (ref "U22") (pin "8") (pinfunction "TOSC1/PB3_8") (pintype "unspecified"))
    )
    (net (code "101") (name "SCL") (class "Default")
      (node (ref "R26") (pin "1") (pinfunction "1_1") (pintype "input"))
      (node (ref "U15") (pin "7") (pinfunction "GPIO5_7") (pintype "bidirectional"))
      (node (ref "U20") (pin "4") (pinfunction "SCL_4") (pintype "unspecified"))
      (node (ref "U24") (pin "14") (pinfunction "SCL_14") (pintype "unspecified"))
    )
    (net (code "102") (name "SDA") (class "Default")
      (node (ref "R22") (pin "1") (pinfunction "1_1") (pintype "input"))
      (node (ref "U15") (pin "6") (pinfunction "GPIO4_6") (pintype "bidirectional"))
      (node (ref "U20") (pin "3") (pinfunction "SDA_3") (pintype "unspecified"))
      (node (ref "U24") (pin "15") (pinfunction "SDA_15") (pintype "unspecified"))
    )
    (net (code "103") (name "SWC") (class "Default")
      (node (ref "S1") (pin "1") (pinfunction "1_1") (pintype "unspecified"))
      (node (ref "U15") (pin "24") (pinfunction "SWCLK_24") (pintype "output"))
    )
    (net (code "104") (name "SWD") (class "Default")
      (node (ref "S1") (pin "3") (pinfunction "3_3") (pintype "unspecified"))
      (node (ref "U15") (pin "25") (pinfunction "SWD_25") (pintype "bidirectional"))
    )
    (net (code "105") (name "T0") (class "Default")
      (node (ref "R23") (pin "1") (pinfunction "1_1") (pintype "input"))
      (node (ref "U14") (pin "2") (pinfunction "2_2") (pintype "unspecified"))
      (node (ref "U22") (pin "3") (pinfunction "PA5_3") (pintype "unspecified"))
    )
    (net (code "106") (name "T1") (class "Default")
      (node (ref "R28") (pin "1") (pinfunction "1_1") (pintype "input"))
      (node (ref "U16") (pin "2") (pinfunction "2_2") (pintype "unspecified"))
      (node (ref "U22") (pin "4") (pinfunction "PA6_4") (pintype "unspecified"))
    )
    (net (code "107") (name "T2") (class "Default")
      (node (ref "R31") (pin "1") (pinfunction "1_1") (pintype "input"))
      (node (ref "U19") (pin "2") (pinfunction "2_2") (pintype "unspecified"))
      (node (ref "U22") (pin "5") (pinfunction "PA7_5") (pintype "unspecified"))
    )
    (net (code "108") (name "T3") (class "Default")
      (node (ref "R32") (pin "1") (pinfunction "1_1") (pintype "input"))
      (node (ref "U21") (pin "2") (pinfunction "2_2") (pintype "unspecified"))
      (node (ref "U22") (pin "6") (pinfunction "PB5_6") (pintype "unspecified"))
    )
    (net (code "109") (name "T4") (class "Default")
      (node (ref "R36") (pin "1") (pinfunction "1_1") (pintype "input"))
      (node (ref "U22") (pin "7") (pinfunction "PB4_7") (pintype "unspecified"))
      (node (ref "U23") (pin "2") (pinfunction "2_2") (pintype "unspecified"))
    )
    (net (code "110") (name "T5") (class "Default")
      (node (ref "R38") (pin "1") (pinfunction "1_1") (pintype "input"))
      (node (ref "U22") (pin "10") (pinfunction "PB1_10") (pintype "unspecified"))
      (node (ref "U25") (pin "2") (pinfunction "2_2") (pintype "unspecified"))
    )
    (net (code "111") (name "T6") (class "Default")
      (node (ref "R44") (pin "1") (pinfunction "1_1") (pintype "input"))
      (node (ref "U22") (pin "13") (pinfunction "PC1_13") (pintype "unspecified"))
      (node (ref "U26") (pin "2") (pinfunction "2_2") (pintype "unspecified"))
    )
    (net (code "112") (name "T7") (class "Default")
      (node (ref "R50") (pin "1") (pinfunction "1_1") (pintype "input"))
      (node (ref "U22") (pin "12") (pinfunction "PC0_12") (pintype "unspecified"))
      (node (ref "U27") (pin "2") (pinfunction "2_2") (pintype "unspecified"))
    )
    (net (code "113") (name "T8") (class "Default")
      (node (ref "R51") (pin "1") (pinfunction "1_1") (pintype "input"))
      (node (ref "U22") (pin "11") (pinfunction "PB0_11") (pintype "unspecified"))
      (node (ref "U28") (pin "2") (pinfunction "2_2") (pintype "unspecified"))
    )
    (net (code "114") (name "T_INT") (class "Default")
      (node (ref "R53") (pin "1") (pinfunction "1_1") (pintype "input"))
      (node (ref "U15") (pin "34") (pinfunction "GPIO22_34") (pintype "bidirectional"))
      (node (ref "U22") (pin "14") (pinfunction "PC2_14") (pintype "unspecified"))
    )
    (net (code "115") (name "T_Rx") (class "Default")
      (node (ref "R35") (pin "1") (pinfunction "1_1") (pintype "input"))
      (node (ref "U15") (pin "12") (pinfunction "GPIO9_12") (pintype "bidirectional"))
      (node (ref "U22") (pin "17") (pinfunction "PA1_17") (pintype "unspecified"))
      (node (ref "U41") (pin "1") (pinfunction "1_1") (pintype "unspecified"))
    )
    (net (code "116") (name "T_Tx") (class "Default")
      (node (ref "R33") (pin "1") (pinfunction "1_1") (pintype "input"))
      (node (ref "U15") (pin "11") (pinfunction "GPIO8_11") (pintype "bidirectional"))
      (node (ref "U22") (pin "18") (pinfunction "PA2_18") (pintype "unspecified"))
      (node (ref "U42") (pin "1") (pinfunction "1_1") (pintype "unspecified"))
    )
    (net (code "117") (name "TxD") (class "Default")
      (node (ref "CN1") (pin "4") (pinfunction "4_4") (pintype "unspecified"))
      (node (ref "U22") (pin "9") (pinfunction "TOSC2/PB2_9") (pintype "unspecified"))
    )
    (net (code "118") (name "UPDI") (class "Default")
      (node (ref "CN1") (pin "3") (pinfunction "3_3") (pintype "unspecified"))
      (node (ref "U22") (pin "16") (pinfunction "PA0/RESET#/UPDI_16") (pintype "unspecified"))
    )
    (net (code "119") (name "USB_VCC") (class "Default")
      (node (ref "D6") (pin "2") (pinfunction "A_2") (pintype "unspecified"))
      (node (ref "Q1") (pin "1") (pinfunction "G_1") (pintype "unspecified"))
      (node (ref "R5") (pin "1") (pinfunction "1_1") (pintype "input"))
      (node (ref "USB1") (pin "11") (pinfunction "VBUS_11") (pintype "unspecified"))
      (node (ref "USB1") (pin "2") (pinfunction "VBUS_2") (pintype "unspecified"))
    )
    (net (code "120") (name "VCC") (class "Default")
      (node (ref "C1") (pin "2") (pinfunction "2_2") (pintype "input"))
      (node (ref "U7") (pin "20") (pinfunction "VCCCORE_20") (pintype "unspecified"))
    )
    (net (code "121") (name "VCC_OK") (class "Default")
      (node (ref "R4") (pin "2") (pinfunction "2_2") (pintype "input"))
      (node (ref "U15") (pin "5") (pinfunction "GPIO3_5") (pintype "bidirectional"))
      (node (ref "U7") (pin "19") (pinfunction "VCC_OK_19") (pintype "unspecified"))
    )
    (net (code "122") (name "VDDHV") (class "Default")
      (node (ref "C11") (pin "1") (pinfunction "1_1") (pintype "unspecified"))
      (node (ref "C14") (pin "1") (pinfunction "1_1") (pintype "input"))
      (node (ref "C7") (pin "1") (pinfunction "1_1") (pintype "input"))
      (node (ref "U7") (pin "1") (pinfunction "VDD_REGIN_1") (pintype "unspecified"))
      (node (ref "U7") (pin "14") (pinfunction "DCDC_IN_14") (pintype "unspecified"))
      (node (ref "U7") (pin "9") (pinfunction "VDDHV_9") (pintype "unspecified"))
      (node (ref "U8") (pin "1") (pinfunction "K_1") (pintype "unspecified"))
    )
    (net (code "123") (name "VDDHV_PD") (class "Default")
      (node (ref "U7") (pin "10") (pinfunction "VDDHV_PD_10") (pintype "unspecified"))
      (node (ref "U8") (pin "2") (pinfunction "A_2") (pintype "unspecified"))
    )
    (net (code "124") (name "VFLT") (class "Default")
      (node (ref "C7") (pin "2") (pinfunction "2_2") (pintype "input"))
      (node (ref "C9") (pin "2") (pinfunction "2_2") (pintype "input"))
      (node (ref "U7") (pin "7") (pinfunction "VFLT_7") (pintype "unspecified"))
    )
    (net (code "125") (name "VGATE") (class "Default")
      (node (ref "C8") (pin "2") (pinfunction "2_2") (pintype "input"))
      (node (ref "U7") (pin "13") (pinfunction "VGATE_13") (pintype "unspecified"))
    )
    (net (code "126") (name "unconnected-(R49-Pad3)") (class "Default")
      (node (ref "R49") (pin "3") (pinfunction "3_3") (pintype "unspecified+no_connect"))
    )
    (net (code "127") (name "unconnected-(SW3-EH-Pad6)") (class "Default")
      (node (ref "SW3") (pin "6") (pinfunction "EH_6") (pintype "unspecified+no_connect"))
    )
    (net (code "128") (name "unconnected-(SW3-EH-Pad7)") (class "Default")
      (node (ref "SW3") (pin "7") (pinfunction "EH_7") (pintype "unspecified+no_connect"))
    )
    (net (code "129") (name "unconnected-(U15-GPIO23-Pad35)") (class "Default")
      (node (ref "U15") (pin "35") (pinfunction "GPIO23_35") (pintype "bidirectional+no_connect"))
    )
    (net (code "130") (name "unconnected-(U15-GPIO24-Pad36)") (class "Default")
      (node (ref "U15") (pin "36") (pinfunction "GPIO24_36") (pintype "bidirectional+no_connect"))
    )
    (net (code "131") (name "unconnected-(U15-GPIO26_ADC0-Pad38)") (class "Default")
      (node (ref "U15") (pin "38") (pinfunction "GPIO26_ADC0_38") (pintype "bidirectional+no_connect"))
    )
    (net (code "132") (name "unconnected-(U15-GPIO27_ADC1-Pad39)") (class "Default")
      (node (ref "U15") (pin "39") (pinfunction "GPIO27_ADC1_39") (pintype "bidirectional+no_connect"))
    )
    (net (code "133") (name "unconnected-(U15-GPIO28_ADC2-Pad40)") (class "Default")
      (node (ref "U15") (pin "40") (pinfunction "GPIO28_ADC2_40") (pintype "bidirectional+no_connect"))
    )
    (net (code "134") (name "unconnected-(U15-GPIO29_ADC3-Pad41)") (class "Default")
      (node (ref "U15") (pin "41") (pinfunction "GPIO29_ADC3_41") (pintype "bidirectional+no_connect"))
    )
    (net (code "135") (name "unconnected-(U22-PA3{slash}EXTCLK-Pad19)") (class "Default")
      (node (ref "U22") (pin "19") (pinfunction "PA3/EXTCLK_19") (pintype "unspecified+no_connect"))
    )
    (net (code "136") (name "unconnected-(U24-INT#-Pad13)") (class "Default")
      (node (ref "U24") (pin "13") (pinfunction "INT#_13") (pintype "unspecified+no_connect"))
    )
    (net (code "137") (name "unconnected-(USB1-SBU1-Pad9)") (class "Default")
      (node (ref "USB1") (pin "9") (pinfunction "SBU1_9") (pintype "unspecified+no_connect"))
    )
    (net (code "138") (name "unconnected-(USB1-SBU2-Pad3)") (class "Default")
      (node (ref "USB1") (pin "3") (pinfunction "SBU2_3") (pintype "unspecified+no_connect"))
    )
  )
)
